# XMICRO-MEMORY.net
KiCad netlist of a schematic drawn in EAGLE
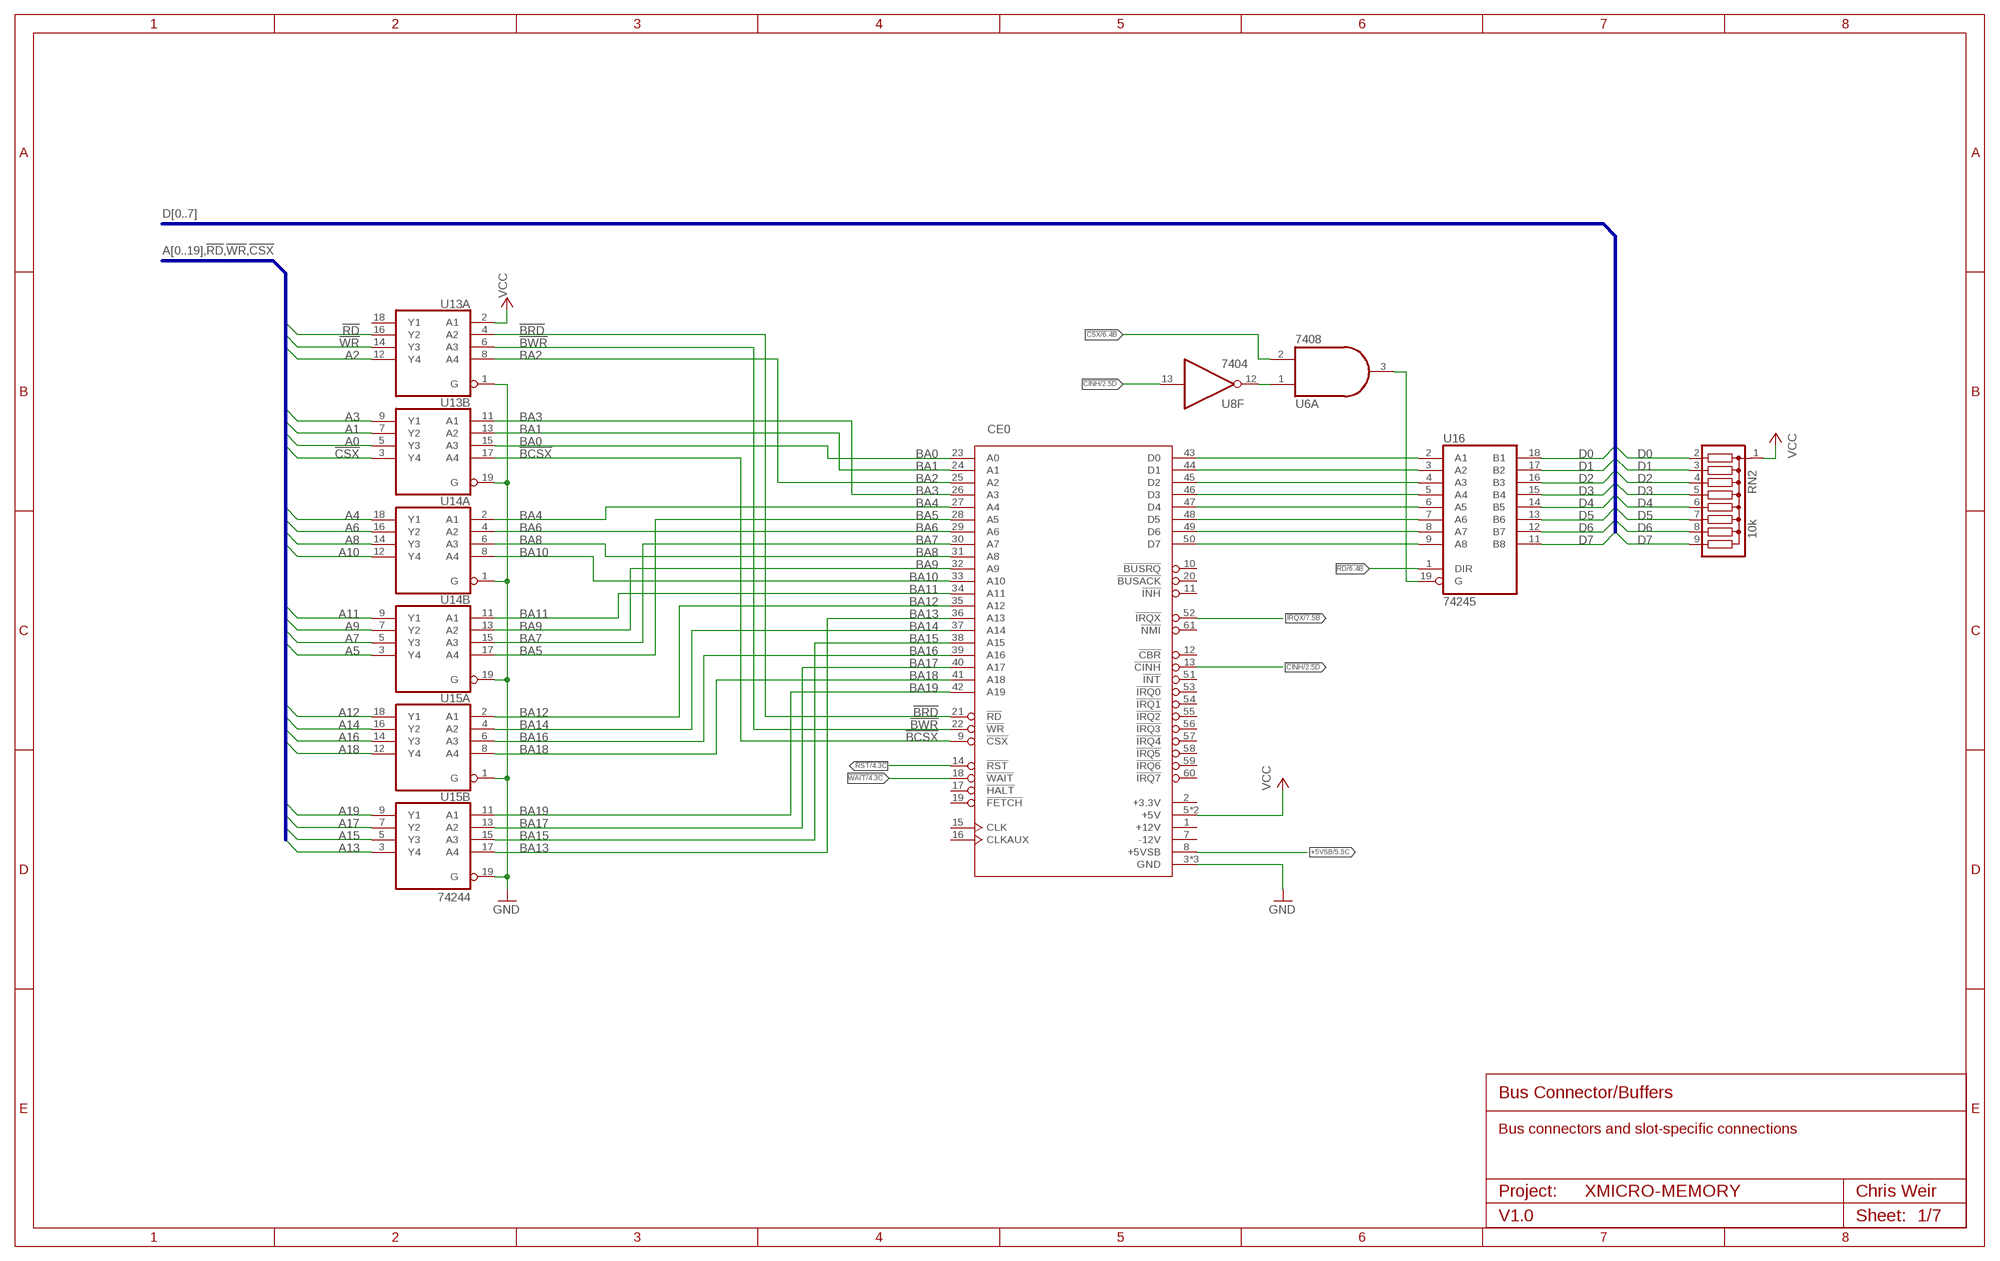
[diagram p0: schematic, sheet 1]
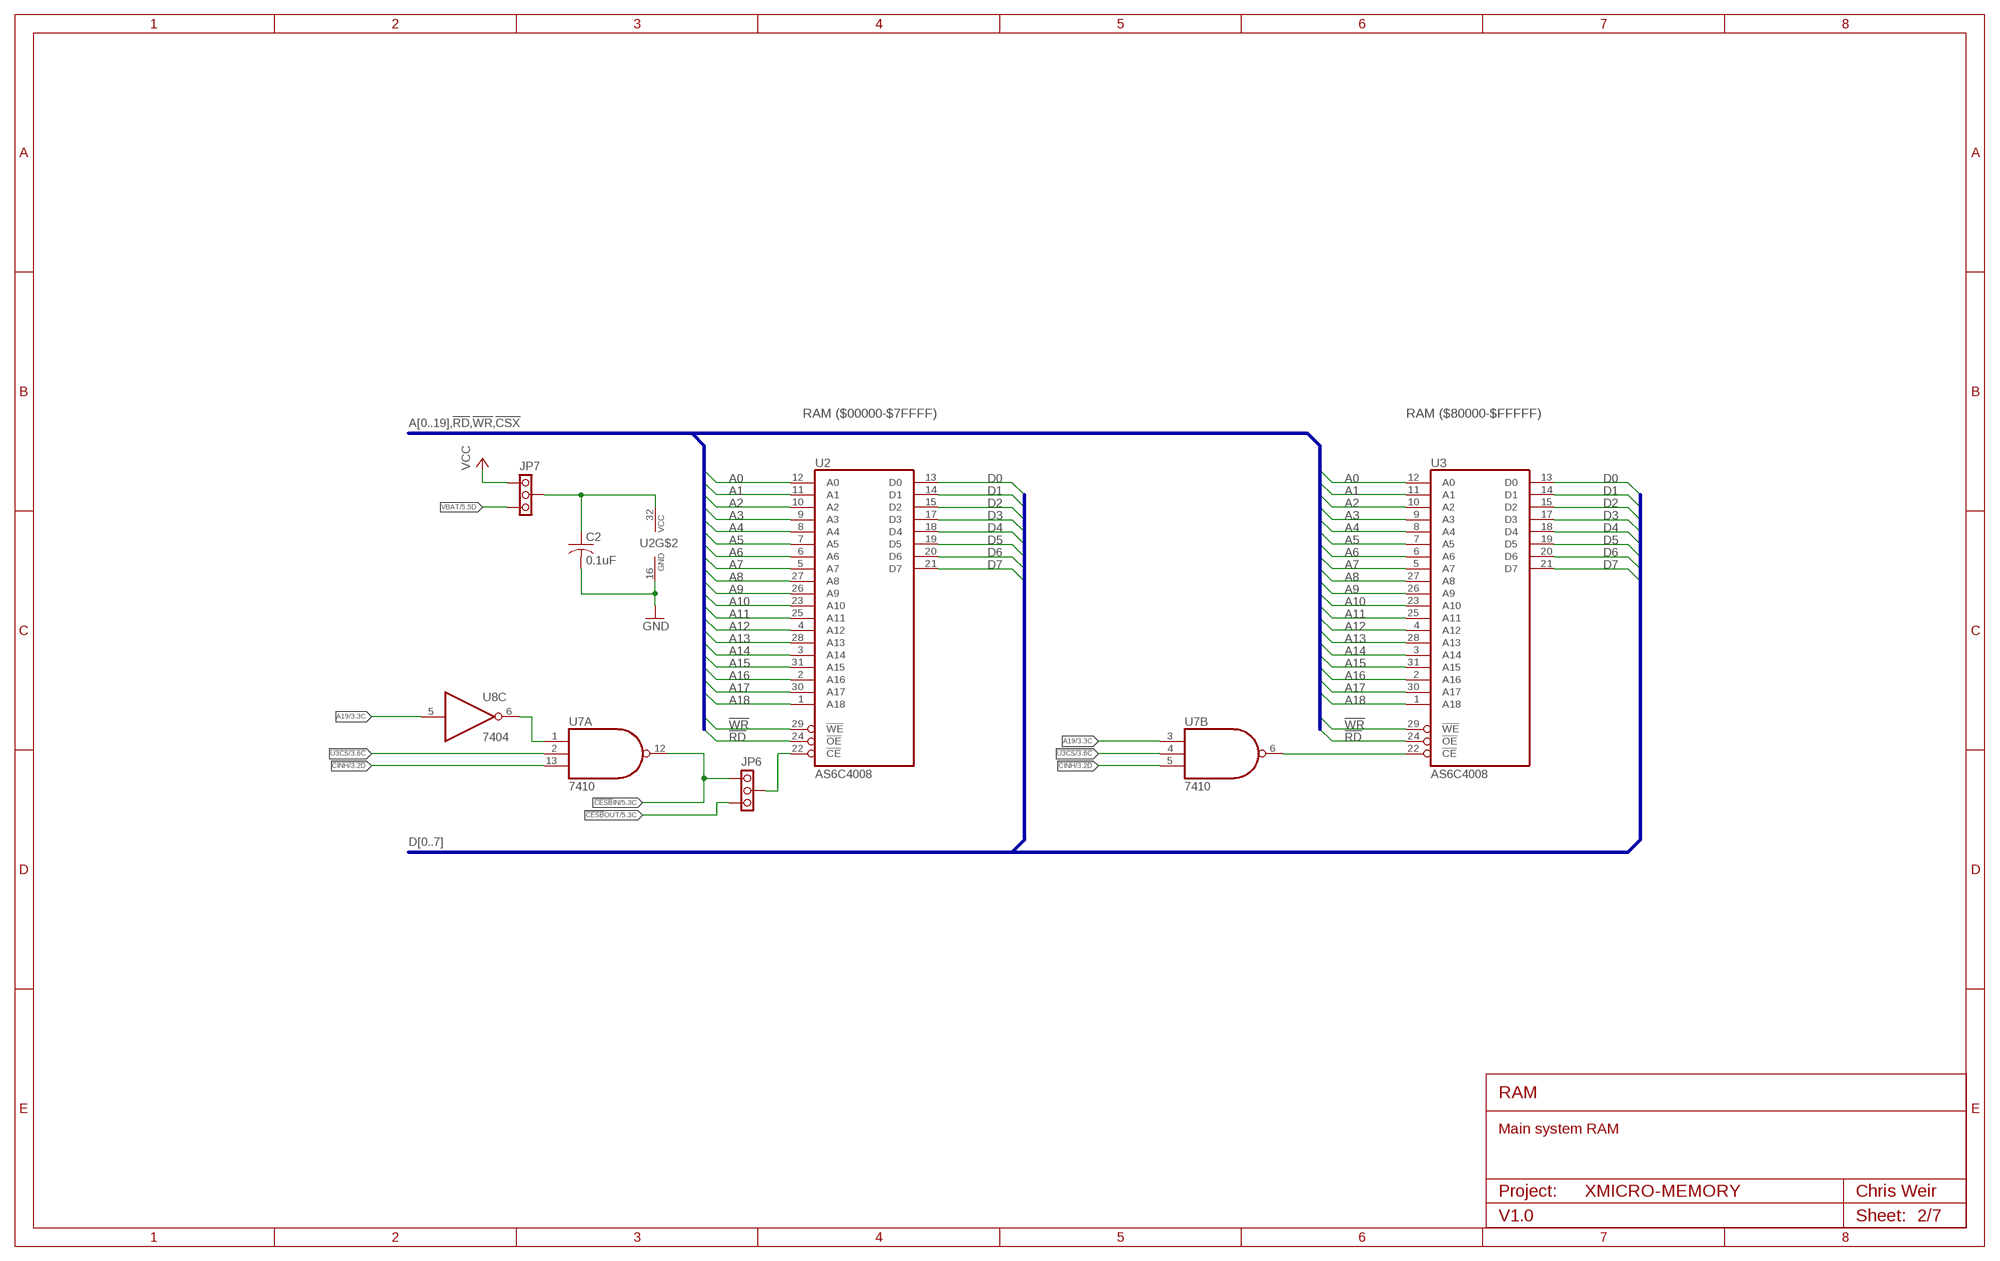
[diagram p1: schematic, sheet 2]
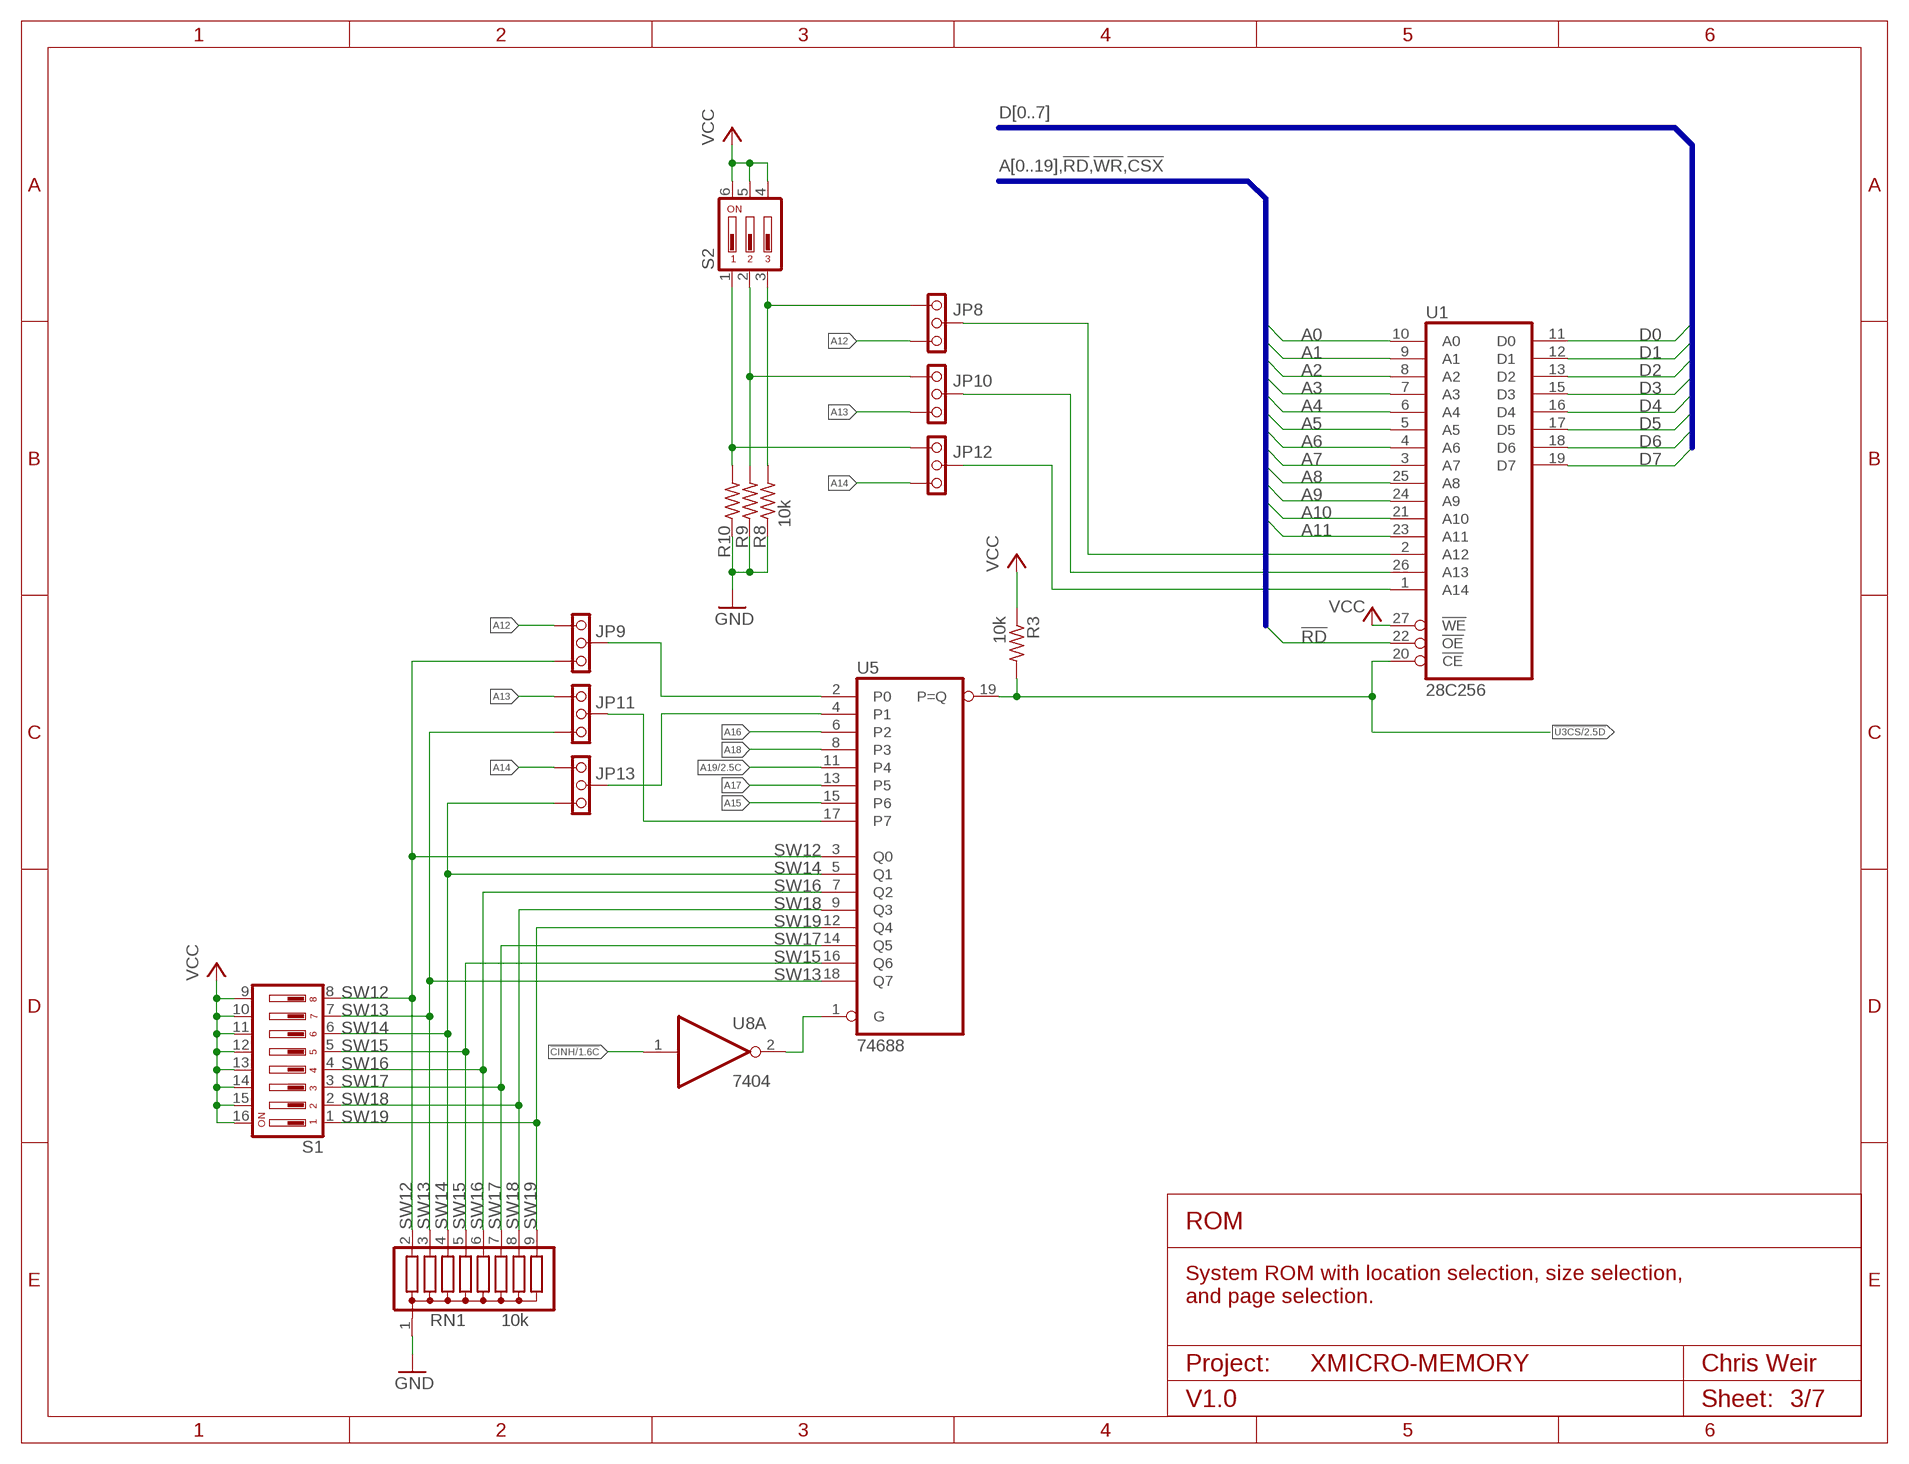
[diagram p2: schematic, sheet 3]
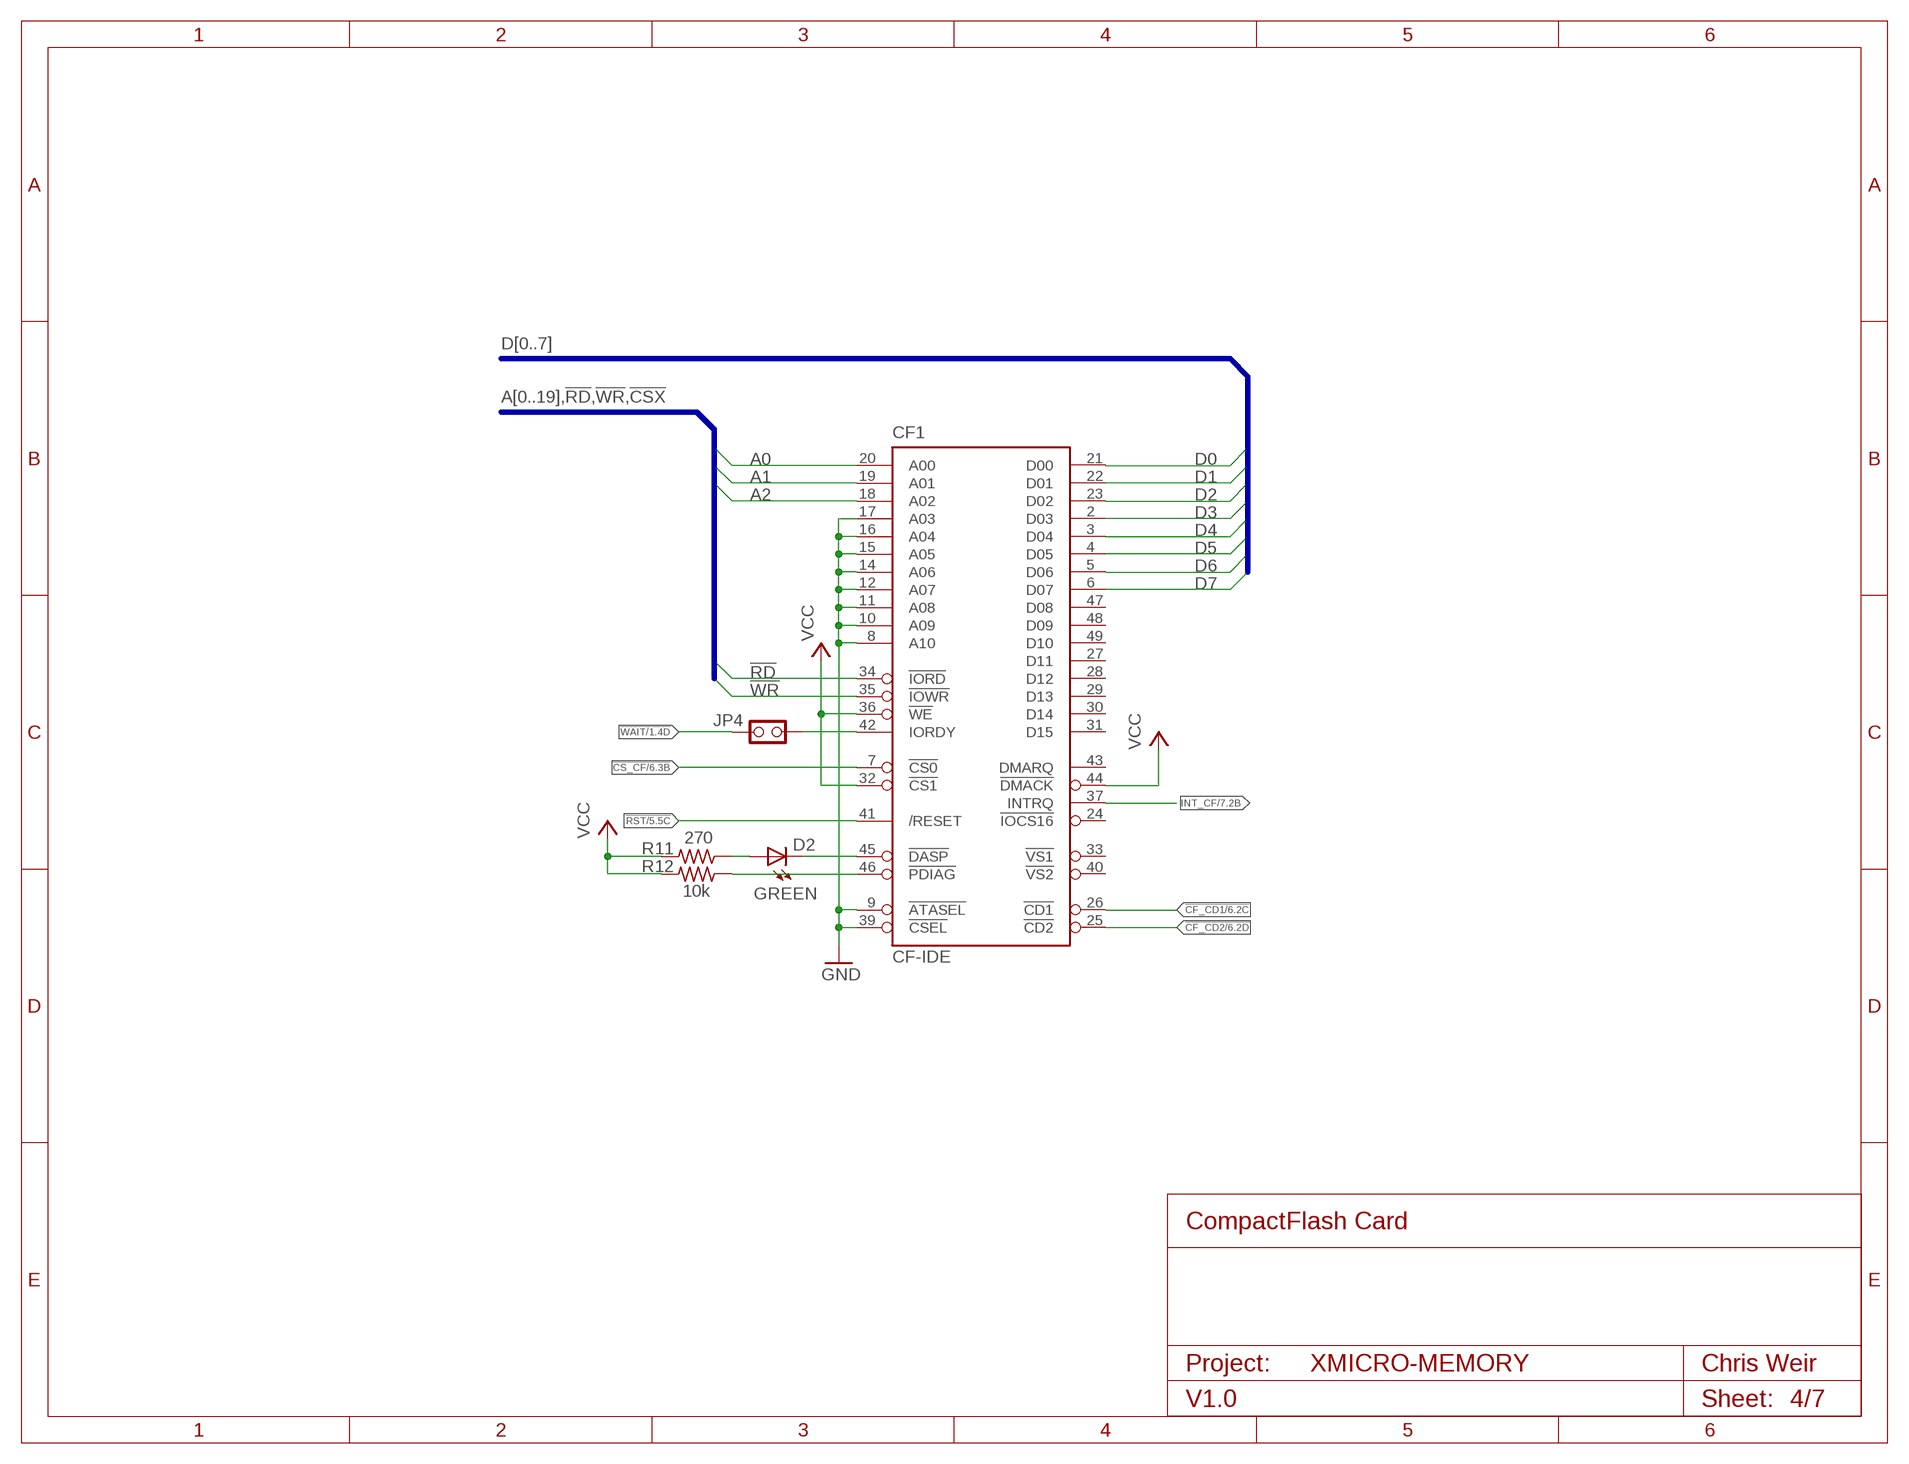
[diagram p3: schematic, sheet 4]
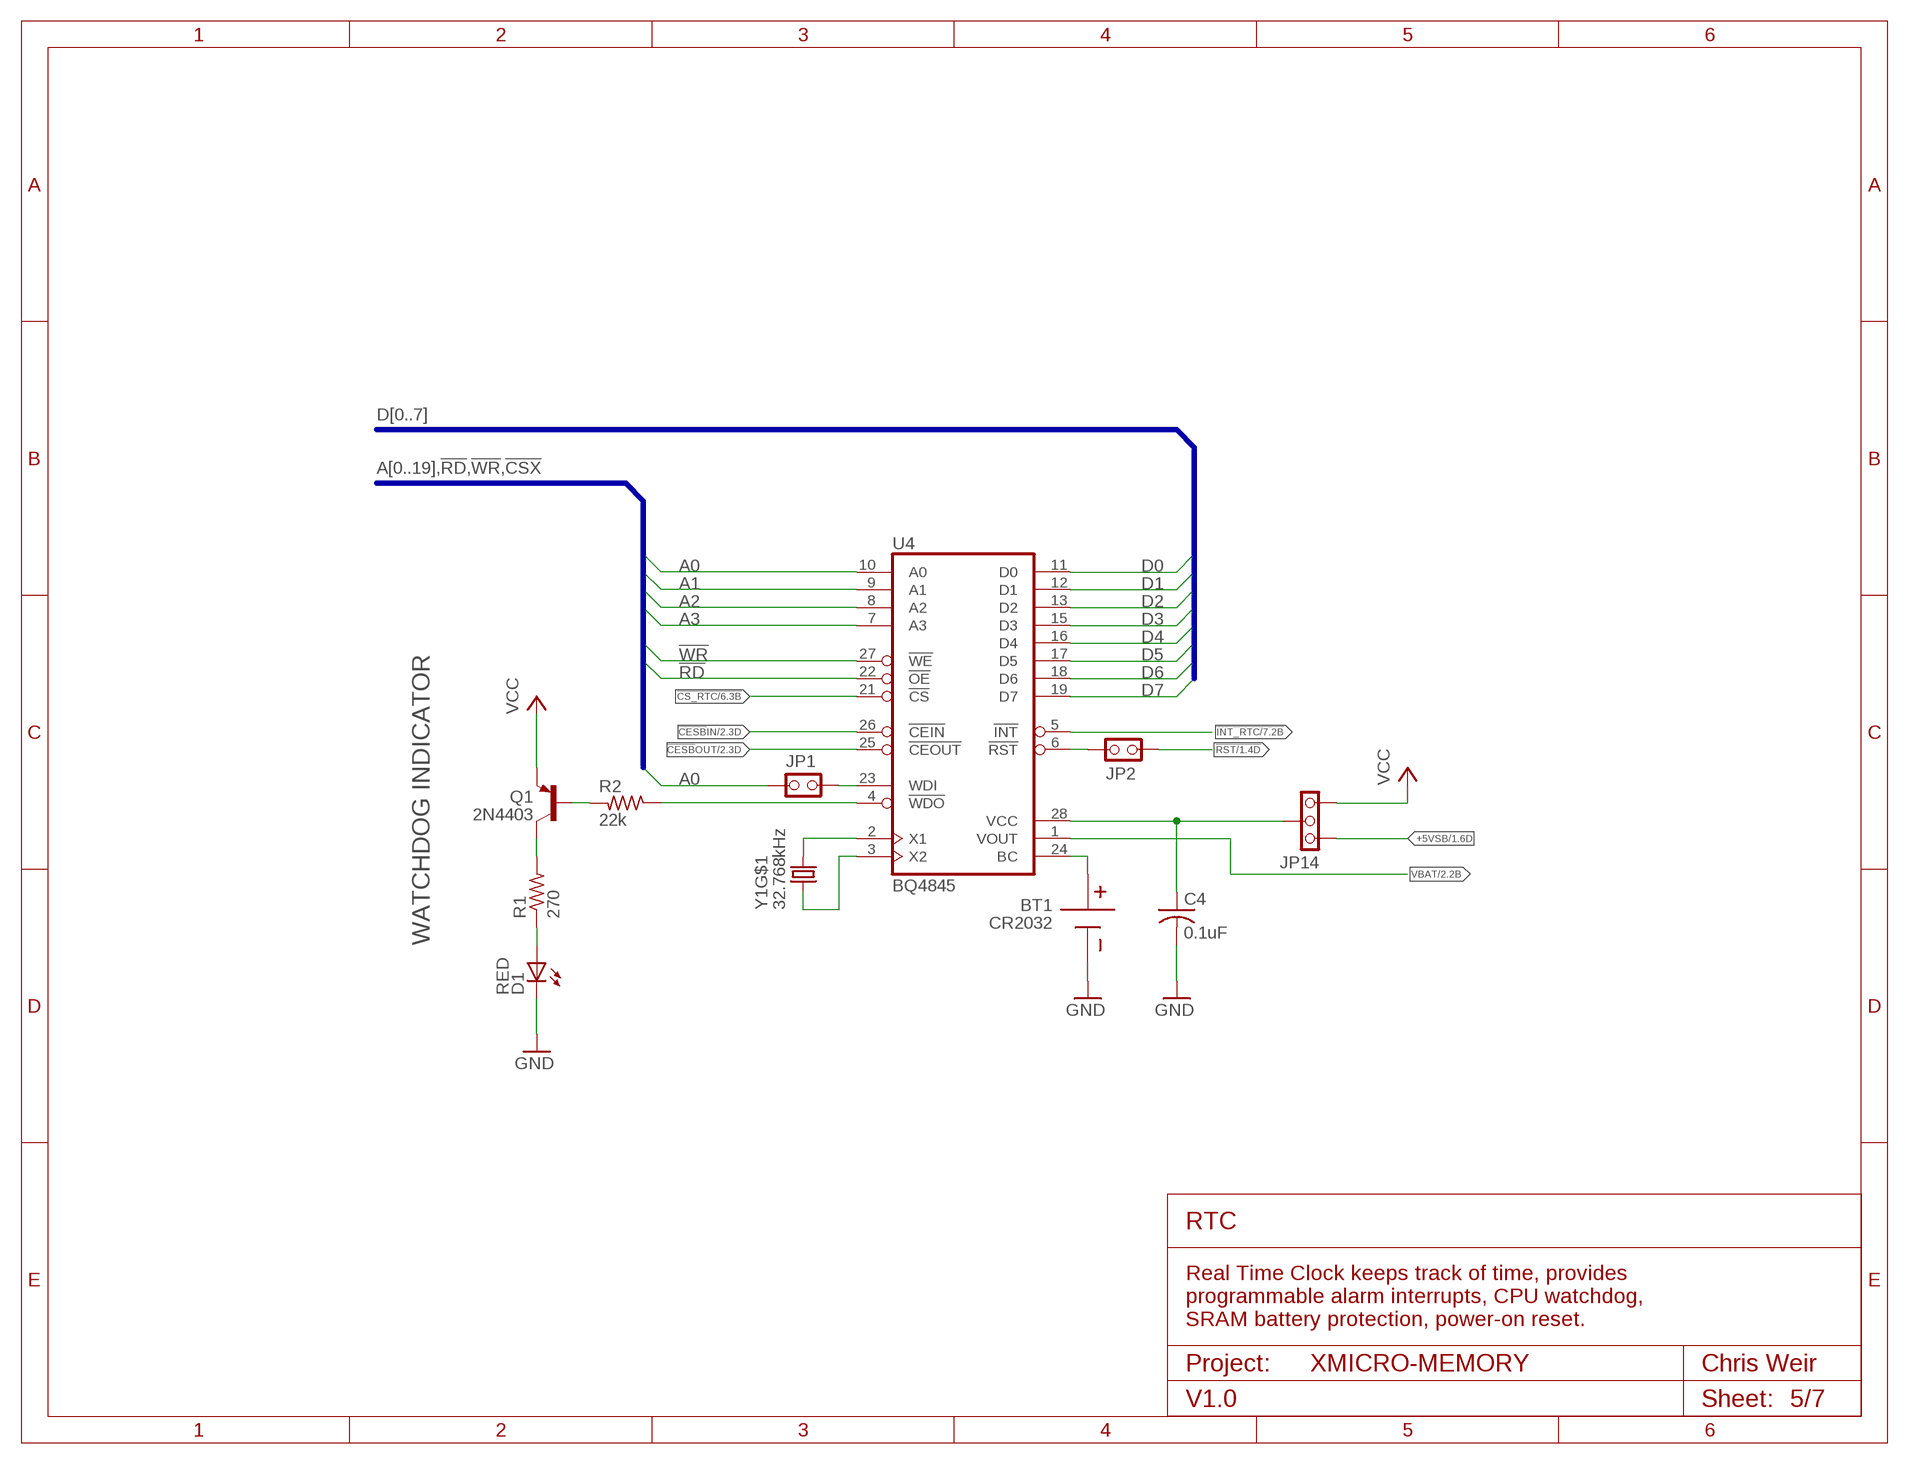
[diagram p4: schematic, sheet 5]
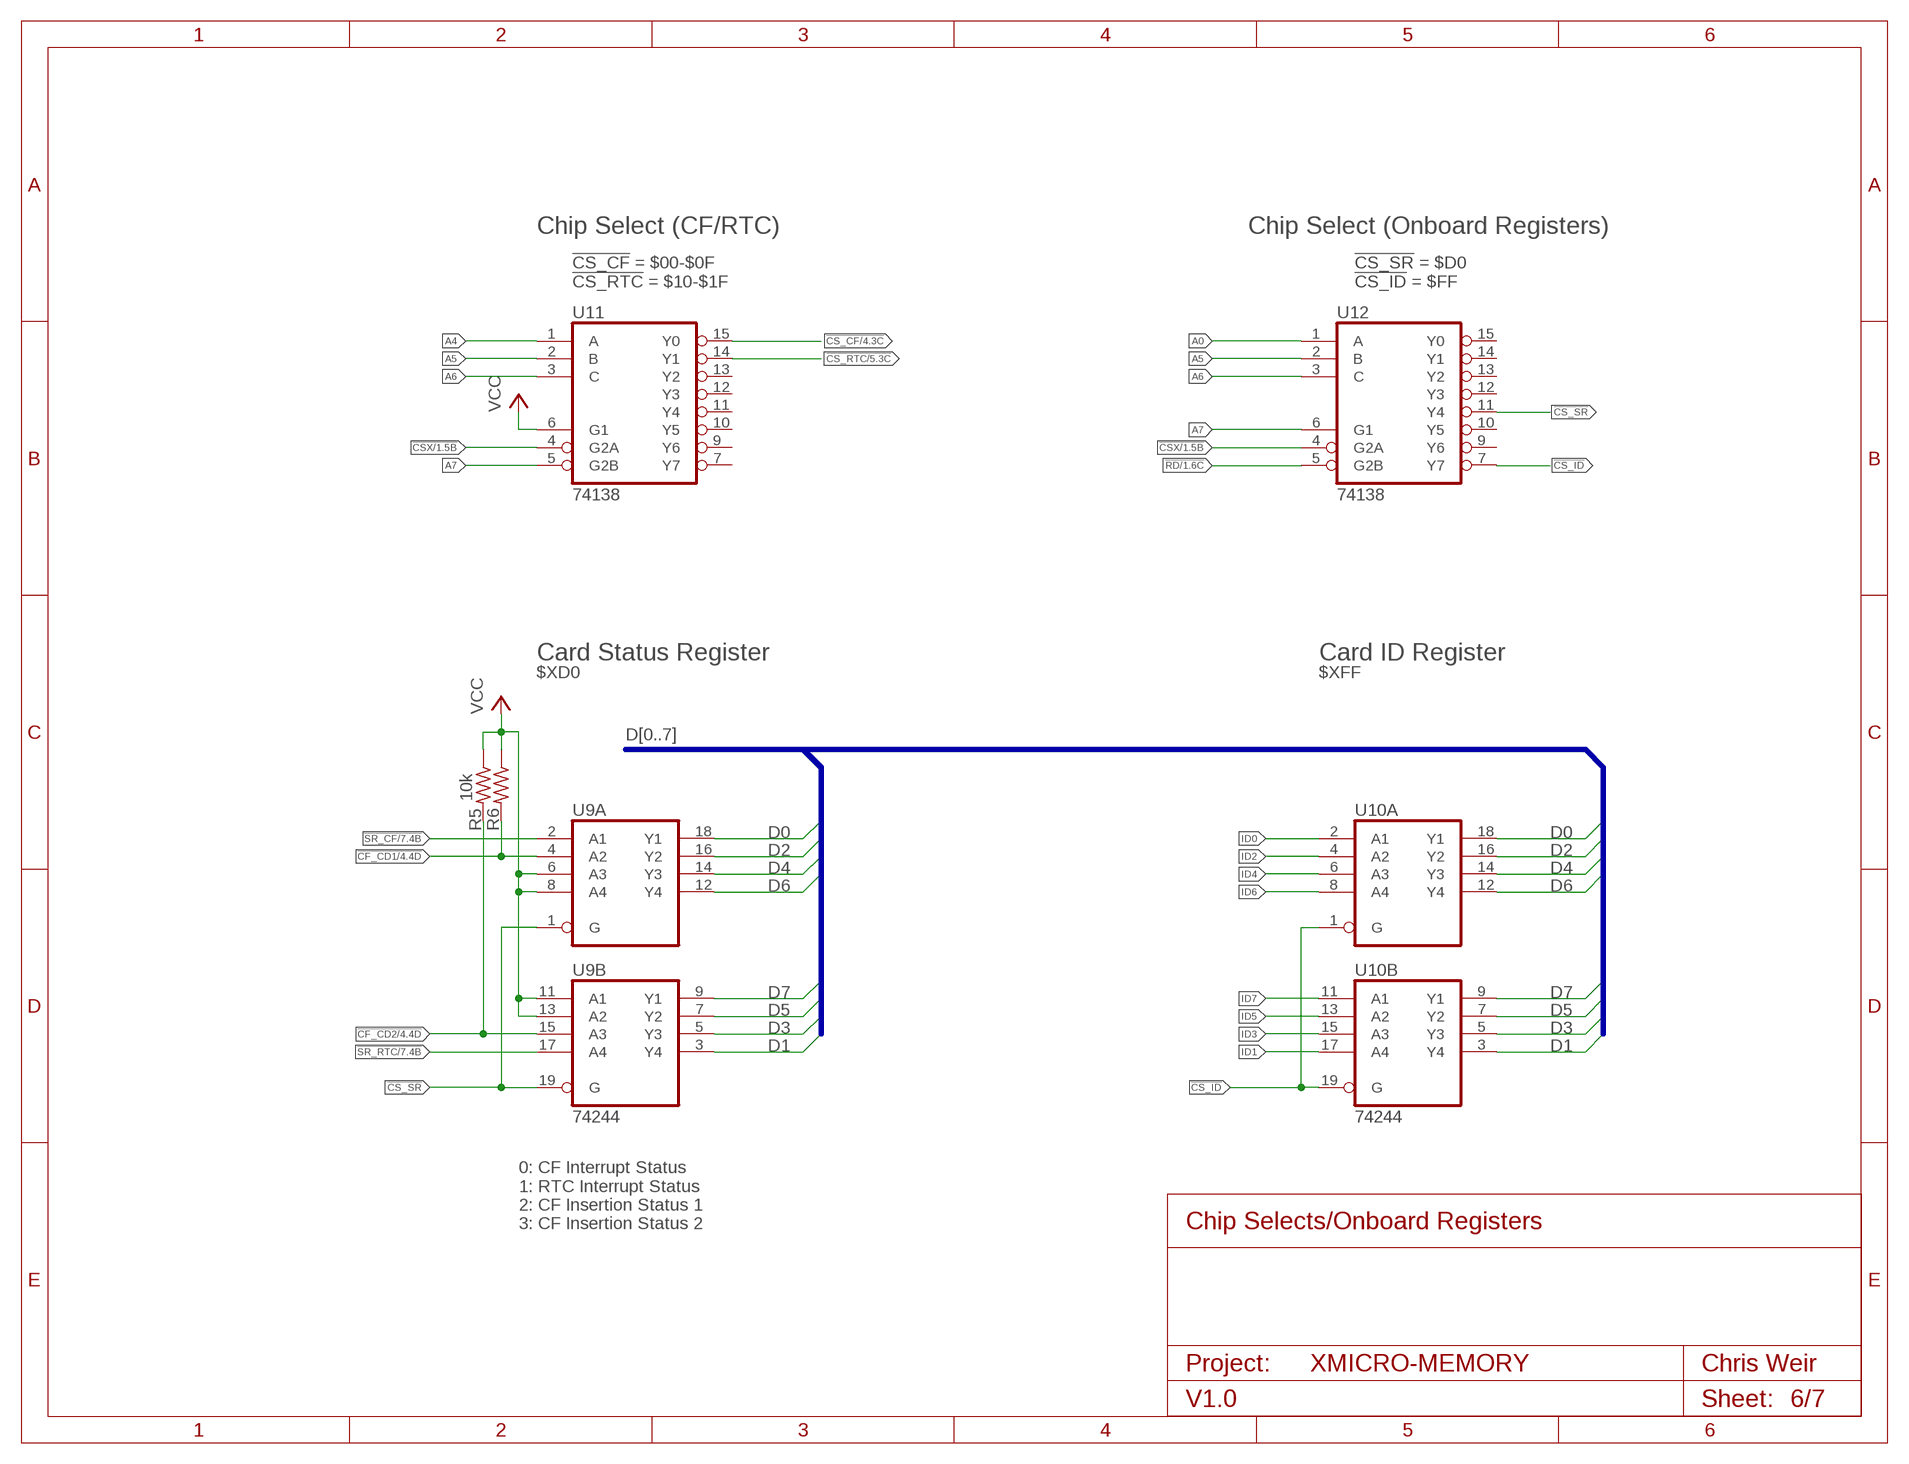
[diagram p5: schematic, sheet 6]
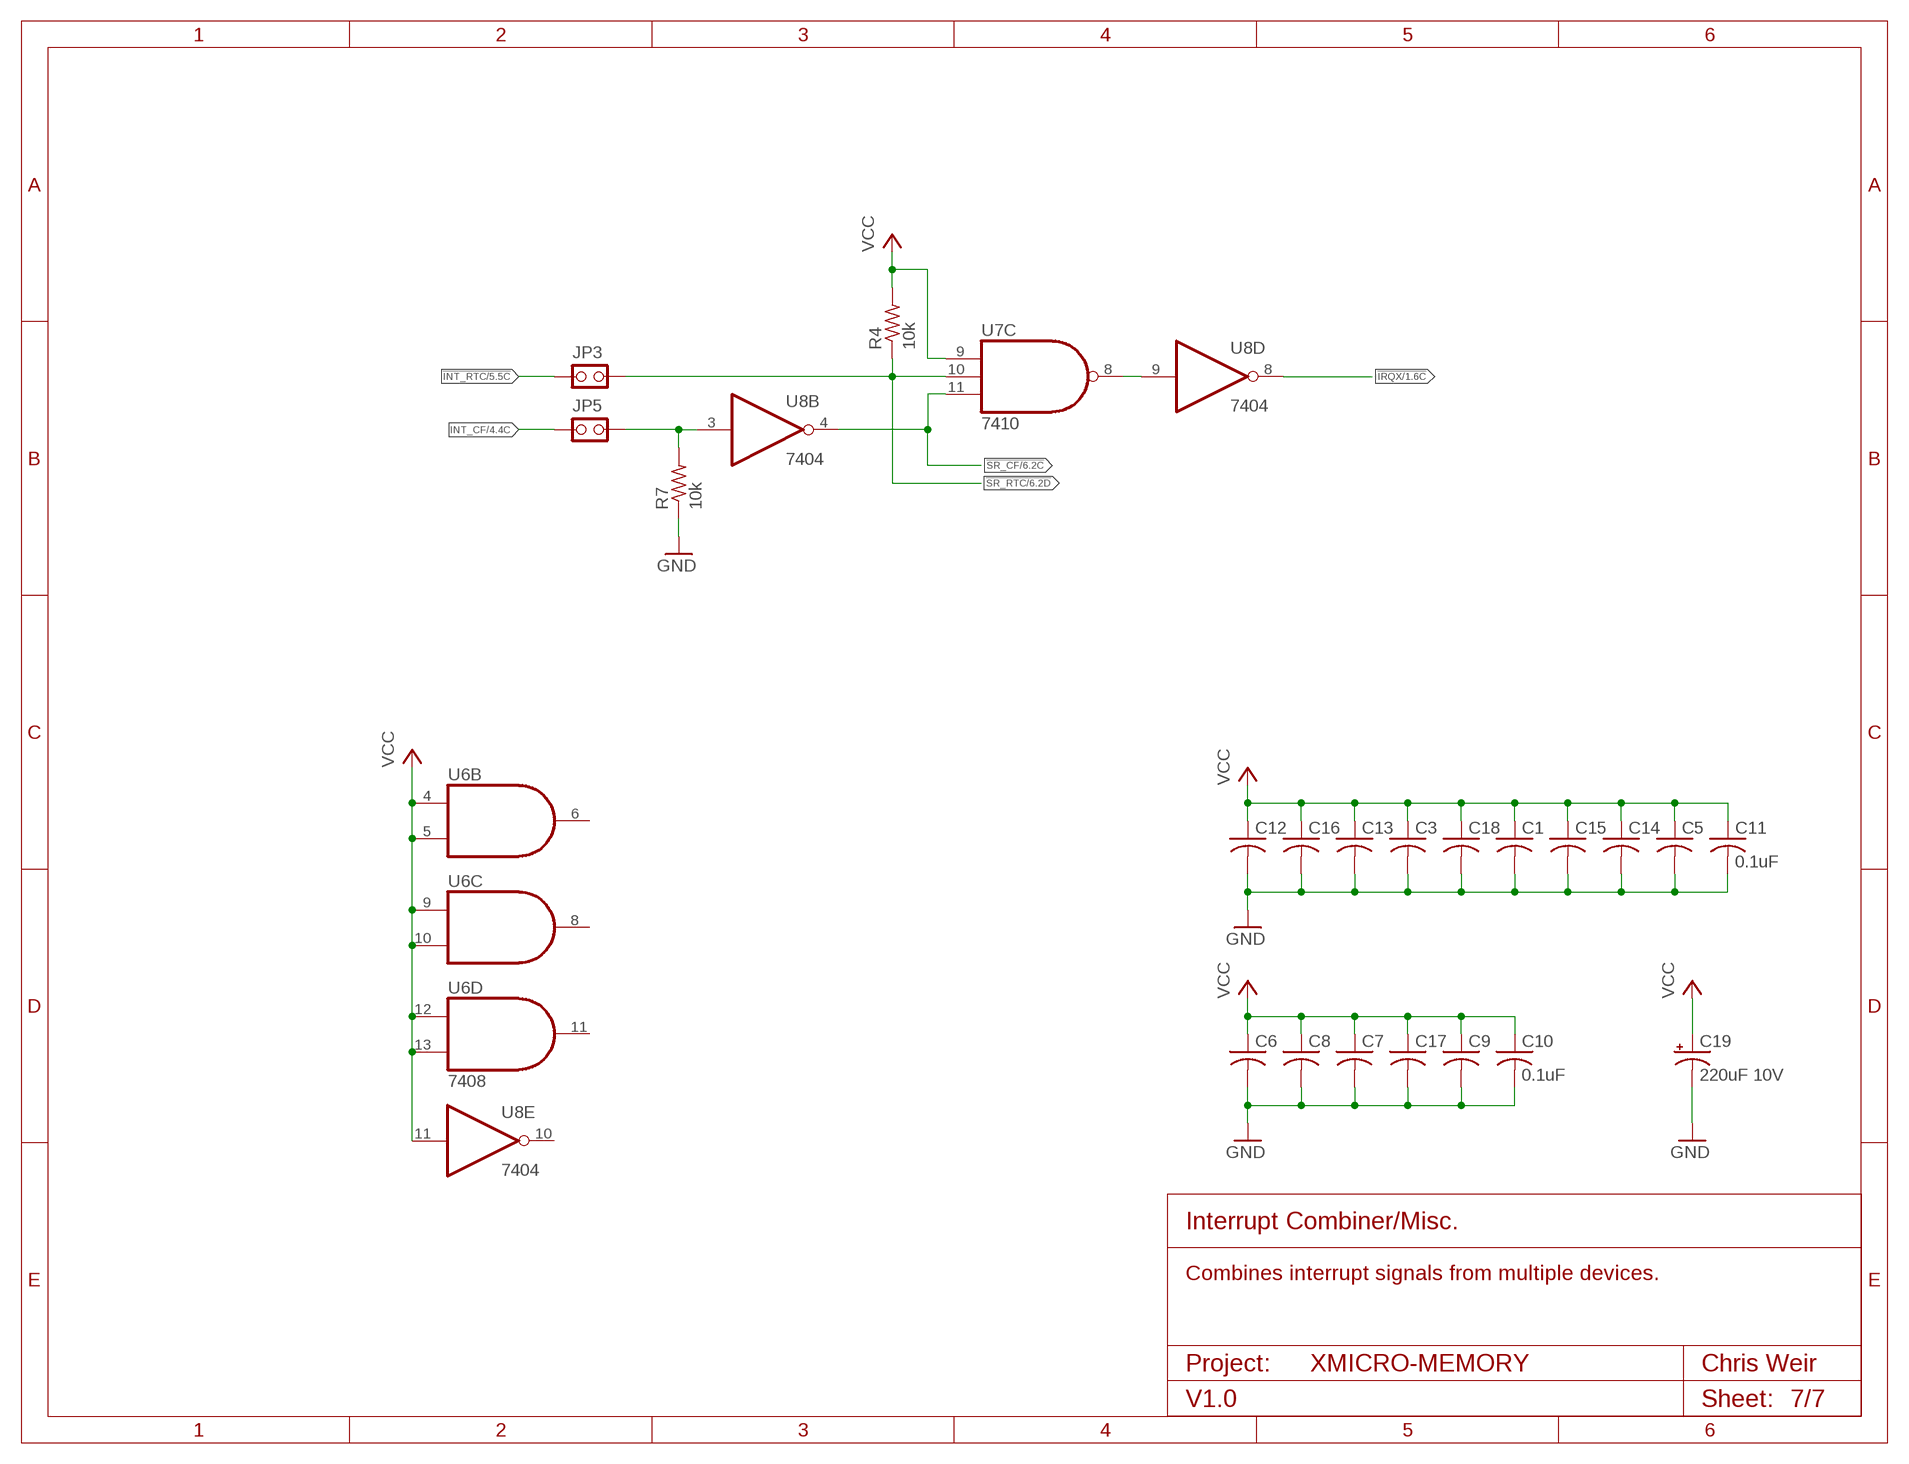
[diagram p6: schematic, sheet 7]

(export (version "E")
  (design (tool "Eeschema 10.0.6"))
  (components
    (comp (ref "CE0")
      (value "XMICRO-BUS-EDGE62M")
      (footprint "eagle-import:EDGE62M")
      (libsource (lib "eagle-import") (part "XMICRO-BUS-EDGE62M"))
    )
    (comp (ref "RN2")
      (value "10k")
      (footprint "eagle-import:SIL9")
      (fields (field (name "OC_FARNELL") "unknown") (field (name "OC_NEWARK") "unknown"))
      (libsource (lib "eagle-import") (part "G08R"))
    )
    (comp (ref "U6")
      (value "7408")
      (footprint "eagle-import:DIL14")
      (libsource (lib "eagle-import") (part "7408NLS"))
    )
    (comp (ref "U8")
      (value "7404")
      (footprint "eagle-import:DIL14")
      (libsource (lib "eagle-import") (part "7404NLS"))
    )
    (comp (ref "U13")
      (value "74244")
      (footprint "eagle-import:DIL20")
      (libsource (lib "eagle-import") (part "74244NLS"))
    )
    (comp (ref "U14")
      (value "74244")
      (footprint "eagle-import:DIL20")
      (libsource (lib "eagle-import") (part "74244NLS"))
    )
    (comp (ref "U15")
      (value "74244")
      (footprint "eagle-import:DIL20")
      (libsource (lib "eagle-import") (part "74244NLS"))
    )
    (comp (ref "U16")
      (value "74245")
      (footprint "eagle-import:DIL20")
      (libsource (lib "eagle-import") (part "74245NLS"))
    )
    (comp (ref "JP8")
      (value "PINHD1X3THRU")
      (footprint "eagle-import:1X03")
      (libsource (lib "eagle-import") (part "PINHD1X3THRU"))
    )
    (comp (ref "JP9")
      (value "PINHD1X3THRU")
      (footprint "eagle-import:1X03")
      (libsource (lib "eagle-import") (part "PINHD1X3THRU"))
    )
    (comp (ref "JP10")
      (value "PINHD1X3THRU")
      (footprint "eagle-import:1X03")
      (libsource (lib "eagle-import") (part "PINHD1X3THRU"))
    )
    (comp (ref "JP11")
      (value "PINHD1X3THRU")
      (footprint "eagle-import:1X03")
      (libsource (lib "eagle-import") (part "PINHD1X3THRU"))
    )
    (comp (ref "JP12")
      (value "PINHD1X3THRU")
      (footprint "eagle-import:1X03")
      (libsource (lib "eagle-import") (part "PINHD1X3THRU"))
    )
    (comp (ref "JP13")
      (value "PINHD1X3THRU")
      (footprint "eagle-import:1X03")
      (libsource (lib "eagle-import") (part "PINHD1X3THRU"))
    )
    (comp (ref "R3")
      (value "10k")
      (footprint "eagle-import:0207_10")
      (libsource (lib "eagle-import") (part "R-US_0207/10"))
    )
    (comp (ref "R8")
      (value "10k")
      (footprint "eagle-import:0207_10")
      (libsource (lib "eagle-import") (part "R-US_0207/10"))
    )
    (comp (ref "R9")
      (value "10k")
      (footprint "eagle-import:0207_10")
      (libsource (lib "eagle-import") (part "R-US_0207/10"))
    )
    (comp (ref "R10")
      (value "10k")
      (footprint "eagle-import:0207_10")
      (libsource (lib "eagle-import") (part "R-US_0207/10"))
    )
    (comp (ref "RN1")
      (value "10k")
      (footprint "eagle-import:SIL9")
      (libsource (lib "eagle-import") (part "G08R"))
    )
    (comp (ref "S1")
      (value "SW-DIP08")
      (footprint "eagle-import:SW-DIP8")
      (libsource (lib "eagle-import") (part "SW-DIP08"))
    )
    (comp (ref "S2")
      (value "SW-DIP03")
      (footprint "eagle-import:SW-DIP3")
      (libsource (lib "eagle-import") (part "SW-DIP03"))
    )
    (comp (ref "U1")
      (value "28C256")
      (footprint "eagle-import:228-1277-00")
      (libsource (lib "eagle-import") (part "28256-ZIF28"))
    )
    (comp (ref "U5")
      (value "74688")
      (footprint "eagle-import:DIL20")
      (libsource (lib "eagle-import") (part "74688NLS"))
    )
    (comp (ref "BT1")
      (value "CR2032")
      (footprint "eagle-import:SMTU2032")
      (libsource (lib "eagle-import") (part "CR2032SMT"))
    )
    (comp (ref "C4")
      (value "0.1uF")
      (footprint "eagle-import:C025-024X044")
      (libsource (lib "eagle-import") (part "C-US025-024X044"))
    )
    (comp (ref "D1")
      (value "RED")
      (footprint "eagle-import:LED5MM")
      (libsource (lib "eagle-import") (part "LED5MM"))
    )
    (comp (ref "JP1")
      (value "PINHD-1X2THRU")
      (footprint "eagle-import:1X02")
      (libsource (lib "eagle-import") (part "PINHD-1X2THRU"))
    )
    (comp (ref "JP2")
      (value "PINHD-1X2THRU")
      (footprint "eagle-import:1X02")
      (libsource (lib "eagle-import") (part "PINHD-1X2THRU"))
    )
    (comp (ref "JP14")
      (value "PINHD1X3THRU")
      (footprint "eagle-import:1X03")
      (libsource (lib "eagle-import") (part "PINHD1X3THRU"))
    )
    (comp (ref "Q1")
      (value "2N4403")
      (footprint "eagle-import:TO92")
      (libsource (lib "eagle-import") (part "TRANSISTOR-PNP-2N4403"))
    )
    (comp (ref "R1")
      (value "270")
      (footprint "eagle-import:0207_10")
      (libsource (lib "eagle-import") (part "R-US_0207/10"))
    )
    (comp (ref "R2")
      (value "22k")
      (footprint "eagle-import:0207_10")
      (libsource (lib "eagle-import") (part "R-US_0207/10"))
    )
    (comp (ref "U4")
      (value "BQ4845")
      (footprint "eagle-import:DIL28")
      (libsource (lib "eagle-import") (part "BQ4845"))
    )
    (comp (ref "Y1")
      (value "32.768kHz")
      (footprint "eagle-import:CRYSTAL-3X8H")
      (libsource (lib "eagle-import") (part "CRYSTAL"))
    )
    (comp (ref "C1")
      (value "0.1uF")
      (footprint "eagle-import:C025-024X044")
      (libsource (lib "eagle-import") (part "C-US025-024X044"))
    )
    (comp (ref "C3")
      (value "0.1uF")
      (footprint "eagle-import:C025-024X044")
      (libsource (lib "eagle-import") (part "C-US025-024X044"))
    )
    (comp (ref "C5")
      (value "0.1uF")
      (footprint "eagle-import:C025-024X044")
      (libsource (lib "eagle-import") (part "C-US025-024X044"))
    )
    (comp (ref "C6")
      (value "0.1uF")
      (footprint "eagle-import:C025-024X044")
      (libsource (lib "eagle-import") (part "C-US025-024X044"))
    )
    (comp (ref "C7")
      (value "0.1uF")
      (footprint "eagle-import:C025-024X044")
      (libsource (lib "eagle-import") (part "C-US025-024X044"))
    )
    (comp (ref "C8")
      (value "0.1uF")
      (footprint "eagle-import:C025-024X044")
      (libsource (lib "eagle-import") (part "C-US025-024X044"))
    )
    (comp (ref "C9")
      (value "0.1uF")
      (footprint "eagle-import:C025-024X044")
      (libsource (lib "eagle-import") (part "C-US025-024X044"))
    )
    (comp (ref "C10")
      (value "0.1uF")
      (footprint "eagle-import:C025-024X044")
      (libsource (lib "eagle-import") (part "C-US025-024X044"))
    )
    (comp (ref "C11")
      (value "0.1uF")
      (footprint "eagle-import:C025-024X044")
      (libsource (lib "eagle-import") (part "C-US025-024X044"))
    )
    (comp (ref "C12")
      (value "0.1uF")
      (footprint "eagle-import:C025-024X044")
      (libsource (lib "eagle-import") (part "C-US025-024X044"))
    )
    (comp (ref "C13")
      (value "0.1uF")
      (footprint "eagle-import:C025-024X044")
      (libsource (lib "eagle-import") (part "C-US025-024X044"))
    )
    (comp (ref "C14")
      (value "0.1uF")
      (footprint "eagle-import:C025-024X044")
      (libsource (lib "eagle-import") (part "C-US025-024X044"))
    )
    (comp (ref "C15")
      (value "0.1uF")
      (footprint "eagle-import:C025-024X044")
      (libsource (lib "eagle-import") (part "C-US025-024X044"))
    )
    (comp (ref "C16")
      (value "0.1uF")
      (footprint "eagle-import:C025-024X044")
      (libsource (lib "eagle-import") (part "C-US025-024X044"))
    )
    (comp (ref "C17")
      (value "0.1uF")
      (footprint "eagle-import:C025-024X044")
      (libsource (lib "eagle-import") (part "C-US025-024X044"))
    )
    (comp (ref "C18")
      (value "0.1uF")
      (footprint "eagle-import:C025-024X044")
      (libsource (lib "eagle-import") (part "C-US025-024X044"))
    )
    (comp (ref "C19")
      (value "220uF 10V")
      (footprint "eagle-import:C-10-5")
      (libsource (lib "eagle-import") (part "CPOL-US-10-5"))
    )
    (comp (ref "JP3")
      (value "PINHD-1X2THRU")
      (footprint "eagle-import:1X02")
      (libsource (lib "eagle-import") (part "PINHD-1X2THRU"))
    )
    (comp (ref "JP5")
      (value "PINHD-1X2THRU")
      (footprint "eagle-import:1X02")
      (libsource (lib "eagle-import") (part "PINHD-1X2THRU"))
    )
    (comp (ref "R4")
      (value "10k")
      (footprint "eagle-import:0207_10")
      (libsource (lib "eagle-import") (part "R-US_0207/10"))
    )
    (comp (ref "R7")
      (value "10k")
      (footprint "eagle-import:0207_10")
      (libsource (lib "eagle-import") (part "R-US_0207/10"))
    )
    (comp (ref "U7")
      (value "7410")
      (footprint "eagle-import:DIL14")
      (libsource (lib "eagle-import") (part "7410NLS"))
    )
    (comp (ref "CF1")
      (value "CF-IDE")
      (footprint "eagle-import:CF-KYOCERA")
      (libsource (lib "eagle-import") (part "CF-IDE"))
    )
    (comp (ref "D2")
      (value "GREEN")
      (footprint "eagle-import:LED-3-R")
      (libsource (lib "eagle-import") (part "LED-3-R"))
    )
    (comp (ref "JP4")
      (value "PINHD-1X2THRU")
      (footprint "eagle-import:1X02")
      (libsource (lib "eagle-import") (part "PINHD-1X2THRU"))
    )
    (comp (ref "R11")
      (value "270")
      (footprint "eagle-import:0207_10")
      (libsource (lib "eagle-import") (part "R-US_0207/10"))
    )
    (comp (ref "R12")
      (value "10k")
      (footprint "eagle-import:0207_10")
      (libsource (lib "eagle-import") (part "R-US_0207/10"))
    )
    (comp (ref "C2")
      (value "0.1uF")
      (footprint "eagle-import:C025-024X044")
      (libsource (lib "eagle-import") (part "C-US025-024X044"))
    )
    (comp (ref "JP6")
      (value "PINHD1X3THRU")
      (footprint "eagle-import:1X03")
      (libsource (lib "eagle-import") (part "PINHD1X3THRU"))
    )
    (comp (ref "JP7")
      (value "PINHD1X3THRU")
      (footprint "eagle-import:1X03")
      (libsource (lib "eagle-import") (part "PINHD1X3THRU"))
    )
    (comp (ref "U2")
      (value "AS6C4008")
      (footprint "eagle-import:DIL32-6")
      (libsource (lib "eagle-import") (part "4008"))
    )
    (comp (ref "U3")
      (value "AS6C4008")
      (footprint "eagle-import:DIL32-6")
      (libsource (lib "eagle-import") (part "4008"))
    )
    (comp (ref "R5")
      (value "10k")
      (footprint "eagle-import:0207_10")
      (libsource (lib "eagle-import") (part "R-US_0207/10"))
    )
    (comp (ref "R6")
      (value "10k")
      (footprint "eagle-import:0207_10")
      (libsource (lib "eagle-import") (part "R-US_0207/10"))
    )
    (comp (ref "U9")
      (value "74244")
      (footprint "eagle-import:DIL20")
      (libsource (lib "eagle-import") (part "74244NLS"))
    )
    (comp (ref "U10")
      (value "74244")
      (footprint "eagle-import:DIL20")
      (libsource (lib "eagle-import") (part "74244NLS"))
    )
    (comp (ref "U11")
      (value "74138")
      (footprint "eagle-import:DIL16")
      (libsource (lib "eagle-import") (part "74138NLS"))
    )
    (comp (ref "U12")
      (value "74138")
      (footprint "eagle-import:DIL16")
      (libsource (lib "eagle-import") (part "74138NLS"))
    )
  )
  (nets
    (net (code "6") (name "+5VSB") (class "Default")
      (node (ref "CE0") (pin "8") (pinfunction "+5VSB_8") (pintype "bidirectional"))
      (node (ref "JP14") (pin "1") (pinfunction "1_1") (pintype "passive"))
    )
    (net (code "18") (name "A0") (class "Default")
      (node (ref "CF1") (pin "20") (pinfunction "A00_20") (pintype "input"))
      (node (ref "JP1") (pin "1") (pinfunction "1_1") (pintype "passive"))
      (node (ref "U1") (pin "10") (pinfunction "A0_10") (pintype "input"))
      (node (ref "U12") (pin "1") (pinfunction "A_1") (pintype "input"))
      (node (ref "U13") (pin "5") (pinfunction "Y3_5") (pintype "tri_state"))
      (node (ref "U2") (pin "12") (pinfunction "A0_12") (pintype "input"))
      (node (ref "U3") (pin "12") (pinfunction "A0_12") (pintype "input"))
      (node (ref "U4") (pin "10") (pinfunction "A0_10") (pintype "input"))
    )
    (net (code "19") (name "A1") (class "Default")
      (node (ref "CF1") (pin "19") (pinfunction "A01_19") (pintype "input"))
      (node (ref "U1") (pin "9") (pinfunction "A1_9") (pintype "input"))
      (node (ref "U13") (pin "7") (pinfunction "Y2_7") (pintype "tri_state"))
      (node (ref "U2") (pin "11") (pinfunction "A1_11") (pintype "input"))
      (node (ref "U3") (pin "11") (pinfunction "A1_11") (pintype "input"))
      (node (ref "U4") (pin "9") (pinfunction "A1_9") (pintype "input"))
    )
    (net (code "20") (name "A2") (class "Default")
      (node (ref "CF1") (pin "18") (pinfunction "A02_18") (pintype "input"))
      (node (ref "U1") (pin "8") (pinfunction "A2_8") (pintype "input"))
      (node (ref "U13") (pin "12") (pinfunction "Y4_12") (pintype "tri_state"))
      (node (ref "U2") (pin "10") (pinfunction "A2_10") (pintype "input"))
      (node (ref "U3") (pin "10") (pinfunction "A2_10") (pintype "input"))
      (node (ref "U4") (pin "8") (pinfunction "A2_8") (pintype "input"))
    )
    (net (code "21") (name "A3") (class "Default")
      (node (ref "U1") (pin "7") (pinfunction "A3_7") (pintype "input"))
      (node (ref "U13") (pin "9") (pinfunction "Y1_9") (pintype "tri_state"))
      (node (ref "U2") (pin "9") (pinfunction "A3_9") (pintype "input"))
      (node (ref "U3") (pin "9") (pinfunction "A3_9") (pintype "input"))
      (node (ref "U4") (pin "7") (pinfunction "A3_7") (pintype "input"))
    )
    (net (code "22") (name "A4") (class "Default")
      (node (ref "U1") (pin "6") (pinfunction "A4_6") (pintype "input"))
      (node (ref "U11") (pin "1") (pinfunction "A_1") (pintype "input"))
      (node (ref "U14") (pin "18") (pinfunction "Y1_18") (pintype "tri_state"))
      (node (ref "U2") (pin "8") (pinfunction "A4_8") (pintype "input"))
      (node (ref "U3") (pin "8") (pinfunction "A4_8") (pintype "input"))
    )
    (net (code "23") (name "A5") (class "Default")
      (node (ref "U1") (pin "5") (pinfunction "A5_5") (pintype "input"))
      (node (ref "U11") (pin "2") (pinfunction "B_2") (pintype "input"))
      (node (ref "U12") (pin "2") (pinfunction "B_2") (pintype "input"))
      (node (ref "U14") (pin "3") (pinfunction "Y4_3") (pintype "tri_state"))
      (node (ref "U2") (pin "7") (pinfunction "A5_7") (pintype "input"))
      (node (ref "U3") (pin "7") (pinfunction "A5_7") (pintype "input"))
    )
    (net (code "24") (name "A6") (class "Default")
      (node (ref "U1") (pin "4") (pinfunction "A6_4") (pintype "input"))
      (node (ref "U11") (pin "3") (pinfunction "C_3") (pintype "input"))
      (node (ref "U12") (pin "3") (pinfunction "C_3") (pintype "input"))
      (node (ref "U14") (pin "16") (pinfunction "Y2_16") (pintype "tri_state"))
      (node (ref "U2") (pin "6") (pinfunction "A6_6") (pintype "input"))
      (node (ref "U3") (pin "6") (pinfunction "A6_6") (pintype "input"))
    )
    (net (code "25") (name "A7") (class "Default")
      (node (ref "U1") (pin "3") (pinfunction "A7_3") (pintype "input"))
      (node (ref "U11") (pin "5") (pinfunction "G2B_5") (pintype "input"))
      (node (ref "U12") (pin "6") (pinfunction "G1_6") (pintype "input"))
      (node (ref "U14") (pin "5") (pinfunction "Y3_5") (pintype "tri_state"))
      (node (ref "U2") (pin "5") (pinfunction "A7_5") (pintype "input"))
      (node (ref "U3") (pin "5") (pinfunction "A7_5") (pintype "input"))
    )
    (net (code "26") (name "A8") (class "Default")
      (node (ref "U1") (pin "25") (pinfunction "A8_25") (pintype "input"))
      (node (ref "U14") (pin "14") (pinfunction "Y3_14") (pintype "tri_state"))
      (node (ref "U2") (pin "27") (pinfunction "A8_27") (pintype "input"))
      (node (ref "U3") (pin "27") (pinfunction "A8_27") (pintype "input"))
    )
    (net (code "27") (name "A9") (class "Default")
      (node (ref "U1") (pin "24") (pinfunction "A9_24") (pintype "input"))
      (node (ref "U14") (pin "7") (pinfunction "Y2_7") (pintype "tri_state"))
      (node (ref "U2") (pin "26") (pinfunction "A9_26") (pintype "input"))
      (node (ref "U3") (pin "26") (pinfunction "A9_26") (pintype "input"))
    )
    (net (code "28") (name "A10") (class "Default")
      (node (ref "U1") (pin "21") (pinfunction "A10_21") (pintype "input"))
      (node (ref "U14") (pin "12") (pinfunction "Y4_12") (pintype "tri_state"))
      (node (ref "U2") (pin "23") (pinfunction "A10_23") (pintype "input"))
      (node (ref "U3") (pin "23") (pinfunction "A10_23") (pintype "input"))
    )
    (net (code "29") (name "A11") (class "Default")
      (node (ref "U1") (pin "23") (pinfunction "A11_23") (pintype "input"))
      (node (ref "U14") (pin "9") (pinfunction "Y1_9") (pintype "tri_state"))
      (node (ref "U2") (pin "25") (pinfunction "A11_25") (pintype "input"))
      (node (ref "U3") (pin "25") (pinfunction "A11_25") (pintype "input"))
    )
    (net (code "30") (name "A12") (class "Default")
      (node (ref "JP8") (pin "3") (pinfunction "3_3") (pintype "passive"))
      (node (ref "JP9") (pin "1") (pinfunction "1_1") (pintype "passive"))
      (node (ref "U15") (pin "18") (pinfunction "Y1_18") (pintype "tri_state"))
      (node (ref "U2") (pin "4") (pinfunction "A12_4") (pintype "input"))
      (node (ref "U3") (pin "4") (pinfunction "A12_4") (pintype "input"))
    )
    (net (code "31") (name "A13") (class "Default")
      (node (ref "JP10") (pin "3") (pinfunction "3_3") (pintype "passive"))
      (node (ref "JP11") (pin "1") (pinfunction "1_1") (pintype "passive"))
      (node (ref "U15") (pin "3") (pinfunction "Y4_3") (pintype "tri_state"))
      (node (ref "U2") (pin "28") (pinfunction "A13_28") (pintype "input"))
      (node (ref "U3") (pin "28") (pinfunction "A13_28") (pintype "input"))
    )
    (net (code "32") (name "A14") (class "Default")
      (node (ref "JP12") (pin "3") (pinfunction "3_3") (pintype "passive"))
      (node (ref "JP13") (pin "1") (pinfunction "1_1") (pintype "passive"))
      (node (ref "U15") (pin "16") (pinfunction "Y2_16") (pintype "tri_state"))
      (node (ref "U2") (pin "3") (pinfunction "A14_3") (pintype "input"))
      (node (ref "U3") (pin "3") (pinfunction "A14_3") (pintype "input"))
    )
    (net (code "33") (name "A15") (class "Default")
      (node (ref "U15") (pin "5") (pinfunction "Y3_5") (pintype "tri_state"))
      (node (ref "U2") (pin "31") (pinfunction "A15_31") (pintype "input"))
      (node (ref "U3") (pin "31") (pinfunction "A15_31") (pintype "input"))
      (node (ref "U5") (pin "15") (pinfunction "P6_15") (pintype "input"))
    )
    (net (code "34") (name "A16") (class "Default")
      (node (ref "U15") (pin "14") (pinfunction "Y3_14") (pintype "tri_state"))
      (node (ref "U2") (pin "2") (pinfunction "A16_2") (pintype "input"))
      (node (ref "U3") (pin "2") (pinfunction "A16_2") (pintype "input"))
      (node (ref "U5") (pin "6") (pinfunction "P2_6") (pintype "input"))
    )
    (net (code "35") (name "A17") (class "Default")
      (node (ref "U15") (pin "7") (pinfunction "Y2_7") (pintype "tri_state"))
      (node (ref "U2") (pin "30") (pinfunction "A17_30") (pintype "input"))
      (node (ref "U3") (pin "30") (pinfunction "A17_30") (pintype "input"))
      (node (ref "U5") (pin "13") (pinfunction "P5_13") (pintype "input"))
    )
    (net (code "36") (name "A18") (class "Default")
      (node (ref "U15") (pin "12") (pinfunction "Y4_12") (pintype "tri_state"))
      (node (ref "U2") (pin "1") (pinfunction "A18_1") (pintype "input"))
      (node (ref "U3") (pin "1") (pinfunction "A18_1") (pintype "input"))
      (node (ref "U5") (pin "8") (pinfunction "P3_8") (pintype "input"))
    )
    (net (code "37") (name "A19") (class "Default")
      (node (ref "U15") (pin "9") (pinfunction "Y1_9") (pintype "tri_state"))
      (node (ref "U5") (pin "11") (pinfunction "P4_11") (pintype "input"))
      (node (ref "U7") (pin "3") (pinfunction "I0_3") (pintype "input"))
      (node (ref "U8") (pin "5") (pinfunction "I_5") (pintype "input"))
    )
    (net (code "38") (name "BA0") (class "Default")
      (node (ref "CE0") (pin "23") (pinfunction "A0_23") (pintype "bidirectional"))
      (node (ref "U13") (pin "15") (pinfunction "A3_15") (pintype "input"))
    )
    (net (code "39") (name "BA1") (class "Default")
      (node (ref "CE0") (pin "24") (pinfunction "A1_24") (pintype "bidirectional"))
      (node (ref "U13") (pin "13") (pinfunction "A2_13") (pintype "input"))
    )
    (net (code "40") (name "BA2") (class "Default")
      (node (ref "CE0") (pin "25") (pinfunction "A2_25") (pintype "bidirectional"))
      (node (ref "U13") (pin "8") (pinfunction "A4_8") (pintype "input"))
    )
    (net (code "41") (name "BA3") (class "Default")
      (node (ref "CE0") (pin "26") (pinfunction "A3_26") (pintype "bidirectional"))
      (node (ref "U13") (pin "11") (pinfunction "A1_11") (pintype "input"))
    )
    (net (code "42") (name "BA4") (class "Default")
      (node (ref "CE0") (pin "27") (pinfunction "A4_27") (pintype "bidirectional"))
      (node (ref "U14") (pin "2") (pinfunction "A1_2") (pintype "input"))
    )
    (net (code "43") (name "BA5") (class "Default")
      (node (ref "CE0") (pin "28") (pinfunction "A5_28") (pintype "bidirectional"))
      (node (ref "U14") (pin "17") (pinfunction "A4_17") (pintype "input"))
    )
    (net (code "44") (name "BA6") (class "Default")
      (node (ref "CE0") (pin "29") (pinfunction "A6_29") (pintype "bidirectional"))
      (node (ref "U14") (pin "4") (pinfunction "A2_4") (pintype "input"))
    )
    (net (code "45") (name "BA7") (class "Default")
      (node (ref "CE0") (pin "30") (pinfunction "A7_30") (pintype "bidirectional"))
      (node (ref "U14") (pin "15") (pinfunction "A3_15") (pintype "input"))
    )
    (net (code "46") (name "BA8") (class "Default")
      (node (ref "CE0") (pin "31") (pinfunction "A8_31") (pintype "bidirectional"))
      (node (ref "U14") (pin "6") (pinfunction "A3_6") (pintype "input"))
    )
    (net (code "47") (name "BA9") (class "Default")
      (node (ref "CE0") (pin "32") (pinfunction "A9_32") (pintype "bidirectional"))
      (node (ref "U14") (pin "13") (pinfunction "A2_13") (pintype "input"))
    )
    (net (code "48") (name "BA10") (class "Default")
      (node (ref "CE0") (pin "33") (pinfunction "A10_33") (pintype "bidirectional"))
      (node (ref "U14") (pin "8") (pinfunction "A4_8") (pintype "input"))
    )
    (net (code "49") (name "BA11") (class "Default")
      (node (ref "CE0") (pin "34") (pinfunction "A11_34") (pintype "bidirectional"))
      (node (ref "U14") (pin "11") (pinfunction "A1_11") (pintype "input"))
    )
    (net (code "50") (name "BA12") (class "Default")
      (node (ref "CE0") (pin "35") (pinfunction "A12_35") (pintype "bidirectional"))
      (node (ref "U15") (pin "2") (pinfunction "A1_2") (pintype "input"))
    )
    (net (code "51") (name "BA13") (class "Default")
      (node (ref "CE0") (pin "36") (pinfunction "A13_36") (pintype "bidirectional"))
      (node (ref "U15") (pin "17") (pinfunction "A4_17") (pintype "input"))
    )
    (net (code "52") (name "BA14") (class "Default")
      (node (ref "CE0") (pin "37") (pinfunction "A14_37") (pintype "bidirectional"))
      (node (ref "U15") (pin "4") (pinfunction "A2_4") (pintype "input"))
    )
    (net (code "53") (name "BA15") (class "Default")
      (node (ref "CE0") (pin "38") (pinfunction "A15_38") (pintype "bidirectional"))
      (node (ref "U15") (pin "15") (pinfunction "A3_15") (pintype "input"))
    )
    (net (code "54") (name "BA16") (class "Default")
      (node (ref "CE0") (pin "39") (pinfunction "A16_39") (pintype "bidirectional"))
      (node (ref "U15") (pin "6") (pinfunction "A3_6") (pintype "input"))
    )
    (net (code "55") (name "BA17") (class "Default")
      (node (ref "CE0") (pin "40") (pinfunction "A17_40") (pintype "bidirectional"))
      (node (ref "U15") (pin "13") (pinfunction "A2_13") (pintype "input"))
    )
    (net (code "56") (name "BA18") (class "Default")
      (node (ref "CE0") (pin "41") (pinfunction "A18_41") (pintype "bidirectional"))
      (node (ref "U15") (pin "8") (pinfunction "A4_8") (pintype "input"))
    )
    (net (code "57") (name "BA19") (class "Default")
      (node (ref "CE0") (pin "42") (pinfunction "A19_42") (pintype "bidirectional"))
      (node (ref "U15") (pin "11") (pinfunction "A1_11") (pintype "input"))
    )
    (net (code "58") (name "D0") (class "Default")
      (node (ref "CF1") (pin "21") (pinfunction "D00_21") (pintype "tri_state"))
      (node (ref "RN2") (pin "2") (pinfunction "2_2") (pintype "passive"))
      (node (ref "U1") (pin "11") (pinfunction "D0_11") (pintype "tri_state"))
      (node (ref "U10") (pin "18") (pinfunction "Y1_18") (pintype "tri_state"))
      (node (ref "U16") (pin "18") (pinfunction "B1_18") (pintype "bidirectional"))
      (node (ref "U2") (pin "13") (pinfunction "D0_13") (pintype "tri_state"))
      (node (ref "U3") (pin "13") (pinfunction "D0_13") (pintype "tri_state"))
      (node (ref "U4") (pin "11") (pinfunction "D0_11") (pintype "tri_state"))
      (node (ref "U9") (pin "18") (pinfunction "Y1_18") (pintype "tri_state"))
    )
    (net (code "59") (name "D1") (class "Default")
      (node (ref "CF1") (pin "22") (pinfunction "D01_22") (pintype "tri_state"))
      (node (ref "RN2") (pin "3") (pinfunction "3_3") (pintype "passive"))
      (node (ref "U1") (pin "12") (pinfunction "D1_12") (pintype "tri_state"))
      (node (ref "U10") (pin "3") (pinfunction "Y4_3") (pintype "tri_state"))
      (node (ref "U16") (pin "17") (pinfunction "B2_17") (pintype "bidirectional"))
      (node (ref "U2") (pin "14") (pinfunction "D1_14") (pintype "tri_state"))
      (node (ref "U3") (pin "14") (pinfunction "D1_14") (pintype "tri_state"))
      (node (ref "U4") (pin "12") (pinfunction "D1_12") (pintype "tri_state"))
      (node (ref "U9") (pin "3") (pinfunction "Y4_3") (pintype "tri_state"))
    )
    (net (code "60") (name "D2") (class "Default")
      (node (ref "CF1") (pin "23") (pinfunction "D02_23") (pintype "tri_state"))
      (node (ref "RN2") (pin "4") (pinfunction "4_4") (pintype "passive"))
      (node (ref "U1") (pin "13") (pinfunction "D2_13") (pintype "tri_state"))
      (node (ref "U10") (pin "16") (pinfunction "Y2_16") (pintype "tri_state"))
      (node (ref "U16") (pin "16") (pinfunction "B3_16") (pintype "bidirectional"))
      (node (ref "U2") (pin "15") (pinfunction "D2_15") (pintype "tri_state"))
      (node (ref "U3") (pin "15") (pinfunction "D2_15") (pintype "tri_state"))
      (node (ref "U4") (pin "13") (pinfunction "D2_13") (pintype "tri_state"))
      (node (ref "U9") (pin "16") (pinfunction "Y2_16") (pintype "tri_state"))
    )
    (net (code "61") (name "D3") (class "Default")
      (node (ref "CF1") (pin "2") (pinfunction "D03_2") (pintype "tri_state"))
      (node (ref "RN2") (pin "5") (pinfunction "5_5") (pintype "passive"))
      (node (ref "U1") (pin "15") (pinfunction "D3_15") (pintype "tri_state"))
      (node (ref "U10") (pin "5") (pinfunction "Y3_5") (pintype "tri_state"))
      (node (ref "U16") (pin "15") (pinfunction "B4_15") (pintype "bidirectional"))
      (node (ref "U2") (pin "17") (pinfunction "D3_17") (pintype "tri_state"))
      (node (ref "U3") (pin "17") (pinfunction "D3_17") (pintype "tri_state"))
      (node (ref "U4") (pin "15") (pinfunction "D3_15") (pintype "tri_state"))
      (node (ref "U9") (pin "5") (pinfunction "Y3_5") (pintype "tri_state"))
    )
    (net (code "62") (name "D4") (class "Default")
      (node (ref "CF1") (pin "3") (pinfunction "D04_3") (pintype "tri_state"))
      (node (ref "RN2") (pin "6") (pinfunction "6_6") (pintype "passive"))
      (node (ref "U1") (pin "16") (pinfunction "D4_16") (pintype "tri_state"))
      (node (ref "U10") (pin "14") (pinfunction "Y3_14") (pintype "tri_state"))
      (node (ref "U16") (pin "14") (pinfunction "B5_14") (pintype "bidirectional"))
      (node (ref "U2") (pin "18") (pinfunction "D4_18") (pintype "tri_state"))
      (node (ref "U3") (pin "18") (pinfunction "D4_18") (pintype "tri_state"))
      (node (ref "U4") (pin "16") (pinfunction "D4_16") (pintype "tri_state"))
      (node (ref "U9") (pin "14") (pinfunction "Y3_14") (pintype "tri_state"))
    )
    (net (code "63") (name "D5") (class "Default")
      (node (ref "CF1") (pin "4") (pinfunction "D05_4") (pintype "tri_state"))
      (node (ref "RN2") (pin "7") (pinfunction "7_7") (pintype "passive"))
      (node (ref "U1") (pin "17") (pinfunction "D5_17") (pintype "tri_state"))
      (node (ref "U10") (pin "7") (pinfunction "Y2_7") (pintype "tri_state"))
      (node (ref "U16") (pin "13") (pinfunction "B6_13") (pintype "bidirectional"))
      (node (ref "U2") (pin "19") (pinfunction "D5_19") (pintype "tri_state"))
      (node (ref "U3") (pin "19") (pinfunction "D5_19") (pintype "tri_state"))
      (node (ref "U4") (pin "17") (pinfunction "D5_17") (pintype "tri_state"))
      (node (ref "U9") (pin "7") (pinfunction "Y2_7") (pintype "tri_state"))
    )
    (net (code "64") (name "D6") (class "Default")
      (node (ref "CF1") (pin "5") (pinfunction "D06_5") (pintype "tri_state"))
      (node (ref "RN2") (pin "8") (pinfunction "8_8") (pintype "passive"))
      (node (ref "U1") (pin "18") (pinfunction "D6_18") (pintype "tri_state"))
      (node (ref "U10") (pin "12") (pinfunction "Y4_12") (pintype "tri_state"))
      (node (ref "U16") (pin "12") (pinfunction "B7_12") (pintype "bidirectional"))
      (node (ref "U2") (pin "20") (pinfunction "D6_20") (pintype "tri_state"))
      (node (ref "U3") (pin "20") (pinfunction "D6_20") (pintype "tri_state"))
      (node (ref "U4") (pin "18") (pinfunction "D6_18") (pintype "tri_state"))
      (node (ref "U9") (pin "12") (pinfunction "Y4_12") (pintype "tri_state"))
    )
    (net (code "65") (name "D7") (class "Default")
      (node (ref "CF1") (pin "6") (pinfunction "D07_6") (pintype "tri_state"))
      (node (ref "RN2") (pin "9") (pinfunction "9_9") (pintype "passive"))
      (node (ref "U1") (pin "19") (pinfunction "D7_19") (pintype "tri_state"))
      (node (ref "U10") (pin "9") (pinfunction "Y1_9") (pintype "tri_state"))
      (node (ref "U16") (pin "11") (pinfunction "B8_11") (pintype "bidirectional"))
      (node (ref "U2") (pin "21") (pinfunction "D7_21") (pintype "tri_state"))
      (node (ref "U3") (pin "21") (pinfunction "D7_21") (pintype "tri_state"))
      (node (ref "U4") (pin "19") (pinfunction "D7_19") (pintype "tri_state"))
      (node (ref "U9") (pin "9") (pinfunction "Y1_9") (pintype "tri_state"))
    )
    (net (code "66") (name "GND") (class "Default")
      (node (ref "BT1") (pin "-") (pinfunction "-_-") (pintype "passive"))
      (node (ref "C1") (pin "2") (pinfunction "2_2") (pintype "passive"))
      (node (ref "C10") (pin "2") (pinfunction "2_2") (pintype "passive"))
      (node (ref "C11") (pin "2") (pinfunction "2_2") (pintype "passive"))
      (node (ref "C12") (pin "2") (pinfunction "2_2") (pintype "passive"))
      (node (ref "C13") (pin "2") (pinfunction "2_2") (pintype "passive"))
      (node (ref "C14") (pin "2") (pinfunction "2_2") (pintype "passive"))
      (node (ref "C15") (pin "2") (pinfunction "2_2") (pintype "passive"))
      (node (ref "C16") (pin "2") (pinfunction "2_2") (pintype "passive"))
      (node (ref "C17") (pin "2") (pinfunction "2_2") (pintype "passive"))
      (node (ref "C18") (pin "2") (pinfunction "2_2") (pintype "passive"))
      (node (ref "C19") (pin "-") (pinfunction "-_-") (pintype "passive"))
      (node (ref "C2") (pin "2") (pinfunction "2_2") (pintype "passive"))
      (node (ref "C3") (pin "2") (pinfunction "2_2") (pintype "passive"))
      (node (ref "C4") (pin "2") (pinfunction "2_2") (pintype "passive"))
      (node (ref "C5") (pin "2") (pinfunction "2_2") (pintype "passive"))
      (node (ref "C6") (pin "2") (pinfunction "2_2") (pintype "passive"))
      (node (ref "C7") (pin "2") (pinfunction "2_2") (pintype "passive"))
      (node (ref "C8") (pin "2") (pinfunction "2_2") (pintype "passive"))
      (node (ref "C9") (pin "2") (pinfunction "2_2") (pintype "passive"))
      (node (ref "CE0") (pin "3") (pinfunction "GND_3") (pintype "bidirectional"))
      (node (ref "CE0") (pin "4") (pinfunction "GND_4") (pintype "bidirectional"))
      (node (ref "CE0") (pin "62") (pinfunction "GND_62") (pintype "bidirectional"))
      (node (ref "CF1") (pin "10") (pinfunction "A09_10") (pintype "input"))
      (node (ref "CF1") (pin "11") (pinfunction "A08_11") (pintype "input"))
      (node (ref "CF1") (pin "12") (pinfunction "A07_12") (pintype "input"))
      (node (ref "CF1") (pin "14") (pinfunction "A06_14") (pintype "input"))
      (node (ref "CF1") (pin "15") (pinfunction "A05_15") (pintype "input"))
      (node (ref "CF1") (pin "16") (pinfunction "A04_16") (pintype "input"))
      (node (ref "CF1") (pin "17") (pinfunction "A03_17") (pintype "input"))
      (node (ref "CF1") (pin "39") (pinfunction "~{CSEL}_39") (pintype "input"))
      (node (ref "CF1") (pin "8") (pinfunction "A10_8") (pintype "input"))
      (node (ref "CF1") (pin "9") (pinfunction "~{ATASEL}_9") (pintype "input"))
      (node (ref "D1") (pin "K") (pinfunction "C_K") (pintype "passive"))
      (node (ref "R10") (pin "1") (pinfunction "1_1") (pintype "passive"))
      (node (ref "R7") (pin "1") (pinfunction "1_1") (pintype "passive"))
      (node (ref "R8") (pin "1") (pinfunction "1_1") (pintype "passive"))
      (node (ref "R9") (pin "1") (pinfunction "1_1") (pintype "passive"))
      (node (ref "RN1") (pin "1") (pinfunction "1_1") (pintype "passive"))
      (node (ref "U13") (pin "1") (pinfunction "G_1") (pintype "input"))
      (node (ref "U13") (pin "19") (pinfunction "G_19") (pintype "input"))
      (node (ref "U14") (pin "1") (pinfunction "G_1") (pintype "input"))
      (node (ref "U14") (pin "19") (pinfunction "G_19") (pintype "input"))
      (node (ref "U15") (pin "1") (pinfunction "G_1") (pintype "input"))
      (node (ref "U15") (pin "19") (pinfunction "G_19") (pintype "input"))
      (node (ref "U2") (pin "16") (pinfunction "GND_16") (pintype "power_in"))
    )
    (net (code "67") (name "ID0") (class "Default")
      (node (ref "U10") (pin "2") (pinfunction "A1_2") (pintype "input"))
    )
    (net (code "68") (name "ID1") (class "Default")
      (node (ref "U10") (pin "17") (pinfunction "A4_17") (pintype "input"))
    )
    (net (code "69") (name "ID2") (class "Default")
      (node (ref "U10") (pin "4") (pinfunction "A2_4") (pintype "input"))
    )
    (net (code "70") (name "ID3") (class "Default")
      (node (ref "U10") (pin "15") (pinfunction "A3_15") (pintype "input"))
    )
    (net (code "71") (name "ID4") (class "Default")
      (node (ref "U10") (pin "6") (pinfunction "A3_6") (pintype "input"))
    )
    (net (code "72") (name "ID5") (class "Default")
      (node (ref "U10") (pin "13") (pinfunction "A2_13") (pintype "input"))
    )
    (net (code "73") (name "ID6") (class "Default")
      (node (ref "U10") (pin "8") (pinfunction "A4_8") (pintype "input"))
    )
    (net (code "74") (name "ID7") (class "Default")
      (node (ref "U10") (pin "11") (pinfunction "A1_11") (pintype "input"))
    )
    (net (code "75") (name "INT_CF") (class "Default")
      (node (ref "CF1") (pin "37") (pinfunction "INTRQ_37") (pintype "output"))
      (node (ref "JP5") (pin "1") (pinfunction "1_1") (pintype "passive"))
    )
    (net (code "76") (name "Net-(CE0-D0)") (class "Default")
      (node (ref "CE0") (pin "43") (pinfunction "D0_43") (pintype "bidirectional"))
      (node (ref "U16") (pin "2") (pinfunction "A1_2") (pintype "bidirectional"))
    )
    (net (code "77") (name "Net-(CE0-D1)") (class "Default")
      (node (ref "CE0") (pin "44") (pinfunction "D1_44") (pintype "bidirectional"))
      (node (ref "U16") (pin "3") (pinfunction "A2_3") (pintype "bidirectional"))
    )
    (net (code "78") (name "Net-(CE0-D2)") (class "Default")
      (node (ref "CE0") (pin "45") (pinfunction "D2_45") (pintype "bidirectional"))
      (node (ref "U16") (pin "4") (pinfunction "A3_4") (pintype "bidirectional"))
    )
    (net (code "79") (name "Net-(CE0-D3)") (class "Default")
      (node (ref "CE0") (pin "46") (pinfunction "D3_46") (pintype "bidirectional"))
      (node (ref "U16") (pin "5") (pinfunction "A4_5") (pintype "bidirectional"))
    )
    (net (code "80") (name "Net-(CE0-D4)") (class "Default")
      (node (ref "CE0") (pin "47") (pinfunction "D4_47") (pintype "bidirectional"))
      (node (ref "U16") (pin "6") (pinfunction "A5_6") (pintype "bidirectional"))
    )
    (net (code "81") (name "Net-(CE0-D5)") (class "Default")
      (node (ref "CE0") (pin "48") (pinfunction "D5_48") (pintype "bidirectional"))
      (node (ref "U16") (pin "7") (pinfunction "A6_7") (pintype "bidirectional"))
    )
    (net (code "82") (name "Net-(CE0-D6)") (class "Default")
      (node (ref "CE0") (pin "49") (pinfunction "D6_49") (pintype "bidirectional"))
      (node (ref "U16") (pin "8") (pinfunction "A7_8") (pintype "bidirectional"))
    )
    (net (code "83") (name "Net-(CE0-D7)") (class "Default")
      (node (ref "CE0") (pin "50") (pinfunction "D7_50") (pintype "bidirectional"))
      (node (ref "U16") (pin "9") (pinfunction "A8_9") (pintype "bidirectional"))
    )
    (net (code "84") (name "Net-(CF1A-IORDY)") (class "Default")
      (node (ref "CF1") (pin "42") (pinfunction "IORDY_42") (pintype "output"))
      (node (ref "JP4") (pin "2") (pinfunction "2_2") (pintype "passive"))
    )
    (net (code "85") (name "Net-(CF1A-~{DASP})") (class "Default")
      (node (ref "CF1") (pin "45") (pinfunction "~{DASP}_45") (pintype "open_collector"))
      (node (ref "D2") (pin "C") (pinfunction "C_C") (pintype "passive"))
    )
    (net (code "86") (name "Net-(CF1A-~{PDIAG})") (class "Default")
      (node (ref "CF1") (pin "46") (pinfunction "~{PDIAG}_46") (pintype "output"))
      (node (ref "R12") (pin "1") (pinfunction "1_1") (pintype "passive"))
    )
    (net (code "87") (name "Net-(D1-PadA)") (class "Default")
      (node (ref "D1") (pin "A") (pinfunction "A_A") (pintype "passive"))
      (node (ref "R1") (pin "1") (pinfunction "1_1") (pintype "passive"))
    )
    (net (code "88") (name "Net-(D2-PadA)") (class "Default")
      (node (ref "D2") (pin "A") (pinfunction "A_A") (pintype "passive"))
      (node (ref "R11") (pin "1") (pinfunction "1_1") (pintype "passive"))
    )
    (net (code "89") (name "Net-(JP8-Pad1)") (class "Default")
      (node (ref "JP8") (pin "1") (pinfunction "1_1") (pintype "passive"))
      (node (ref "R8") (pin "2") (pinfunction "2_2") (pintype "passive"))
      (node (ref "S2") (pin "3") (pinfunction "3_3") (pintype "passive"))
    )
    (net (code "90") (name "Net-(JP10-Pad1)") (class "Default")
      (node (ref "JP10") (pin "1") (pinfunction "1_1") (pintype "passive"))
      (node (ref "R9") (pin "2") (pinfunction "2_2") (pintype "passive"))
      (node (ref "S2") (pin "2") (pinfunction "2_2") (pintype "passive"))
    )
    (net (code "91") (name "Net-(JP12-Pad1)") (class "Default")
      (node (ref "JP12") (pin "1") (pinfunction "1_1") (pintype "passive"))
      (node (ref "R10") (pin "2") (pinfunction "2_2") (pintype "passive"))
      (node (ref "S2") (pin "1") (pinfunction "1_1") (pintype "passive"))
    )
    (net (code "92") (name "Net-(Q1-B)") (class "Default")
      (node (ref "Q1") (pin "2") (pinfunction "B_2") (pintype "passive"))
      (node (ref "R2") (pin "2") (pinfunction "2_2") (pintype "passive"))
    )
    (net (code "93") (name "Net-(Q1-C)") (class "Default")
      (node (ref "Q1") (pin "3") (pinfunction "C_3") (pintype "passive"))
      (node (ref "R1") (pin "2") (pinfunction "2_2") (pintype "passive"))
    )
    (net (code "94") (name "Net-(U1A-A12)") (class "Default")
      (node (ref "JP8") (pin "2") (pinfunction "2_2") (pintype "passive"))
      (node (ref "U1") (pin "2") (pinfunction "A12_2") (pintype "input"))
    )
    (net (code "95") (name "Net-(U1A-A13)") (class "Default")
      (node (ref "JP10") (pin "2") (pinfunction "2_2") (pintype "passive"))
      (node (ref "U1") (pin "26") (pinfunction "A13_26") (pintype "input"))
    )
    (net (code "96") (name "Net-(U1A-A14)") (class "Default")
      (node (ref "JP12") (pin "2") (pinfunction "2_2") (pintype "passive"))
      (node (ref "U1") (pin "1") (pinfunction "A14_1") (pintype "input"))
    )
    (net (code "97") (name "Net-(U2A-~{CE})") (class "Default")
      (node (ref "JP6") (pin "2") (pinfunction "2_2") (pintype "passive"))
      (node (ref "U2") (pin "22") (pinfunction "~{CE}_22") (pintype "input"))
    )
    (net (code "98") (name "Net-(U2B-VCC)") (class "Default")
      (node (ref "C2") (pin "1") (pinfunction "1_1") (pintype "passive"))
      (node (ref "JP7") (pin "2") (pinfunction "2_2") (pintype "passive"))
      (node (ref "U2") (pin "32") (pinfunction "VCC_32") (pintype "power_in"))
    )
    (net (code "99") (name "Net-(U3A-~{CE})") (class "Default")
      (node (ref "U3") (pin "22") (pinfunction "~{CE}_22") (pintype "input"))
      (node (ref "U7") (pin "6") (pinfunction "O_6") (pintype "output"))
    )
    (net (code "100") (name "Net-(U4A-BC)") (class "Default")
      (node (ref "BT1") (pin "+") (pinfunction "+_+") (pintype "passive"))
      (node (ref "U4") (pin "24") (pinfunction "BC_24") (pintype "input"))
    )
    (net (code "101") (name "Net-(U4A-VCC)") (class "Default")
      (node (ref "C4") (pin "1") (pinfunction "1_1") (pintype "passive"))
      (node (ref "JP14") (pin "2") (pinfunction "2_2") (pintype "passive"))
      (node (ref "U4") (pin "28") (pinfunction "VCC_28") (pintype "input"))
    )
    (net (code "102") (name "Net-(U4A-WDI)") (class "Default")
      (node (ref "JP1") (pin "2") (pinfunction "2_2") (pintype "passive"))
      (node (ref "U4") (pin "23") (pinfunction "WDI_23") (pintype "input"))
    )
    (net (code "103") (name "Net-(U4A-X1)") (class "Default")
      (node (ref "U4") (pin "2") (pinfunction "X1_2") (pintype "input"))
      (node (ref "Y1") (pin "2") (pinfunction "2_2") (pintype "passive"))
    )
    (net (code "104") (name "Net-(U4A-X2)") (class "Default")
      (node (ref "U4") (pin "3") (pinfunction "X2_3") (pintype "input"))
      (node (ref "Y1") (pin "1") (pinfunction "1_1") (pintype "passive"))
    )
    (net (code "105") (name "Net-(U4A-~{RST})") (class "Default")
      (node (ref "JP2") (pin "1") (pinfunction "1_1") (pintype "passive"))
      (node (ref "U4") (pin "6") (pinfunction "~{RST}_6") (pintype "open_collector"))
    )
    (net (code "106") (name "Net-(U4A-~{WDO})") (class "Default")
      (node (ref "R2") (pin "1") (pinfunction "1_1") (pintype "passive"))
      (node (ref "U4") (pin "4") (pinfunction "~{WDO}_4") (pintype "output"))
    )
    (net (code "107") (name "Net-(U5A-G)") (class "Default")
      (node (ref "U5") (pin "1") (pinfunction "G_1") (pintype "input"))
      (node (ref "U8") (pin "2") (pinfunction "O_2") (pintype "output"))
    )
    (net (code "108") (name "Net-(U5A-P0)") (class "Default")
      (node (ref "JP9") (pin "2") (pinfunction "2_2") (pintype "passive"))
      (node (ref "U5") (pin "2") (pinfunction "P0_2") (pintype "input"))
    )
    (net (code "109") (name "Net-(U5A-P1)") (class "Default")
      (node (ref "JP13") (pin "2") (pinfunction "2_2") (pintype "passive"))
      (node (ref "U5") (pin "4") (pinfunction "P1_4") (pintype "input"))
    )
    (net (code "110") (name "Net-(U5A-P7)") (class "Default")
      (node (ref "JP11") (pin "2") (pinfunction "2_2") (pintype "passive"))
      (node (ref "U5") (pin "17") (pinfunction "P7_17") (pintype "input"))
    )
    (net (code "111") (name "Net-(U6A-I0)") (class "Default")
      (node (ref "U6") (pin "1") (pinfunction "I0_1") (pintype "input"))
      (node (ref "U8") (pin "12") (pinfunction "O_12") (pintype "output"))
    )
    (net (code "112") (name "Net-(U7A-I0)") (class "Default")
      (node (ref "U7") (pin "1") (pinfunction "I0_1") (pintype "input"))
      (node (ref "U8") (pin "6") (pinfunction "O_6") (pintype "output"))
    )
    (net (code "113") (name "Net-(U7C-O)") (class "Default")
      (node (ref "U7") (pin "8") (pinfunction "O_8") (pintype "output"))
      (node (ref "U8") (pin "9") (pinfunction "I_9") (pintype "input"))
    )
    (net (code "114") (name "Net-(U8B-I)") (class "Default")
      (node (ref "JP5") (pin "2") (pinfunction "2_2") (pintype "passive"))
      (node (ref "R7") (pin "2") (pinfunction "2_2") (pintype "passive"))
      (node (ref "U8") (pin "3") (pinfunction "I_3") (pintype "input"))
    )
    (net (code "115") (name "Net-(U16A-G)") (class "Default")
      (node (ref "U16") (pin "19") (pinfunction "G_19") (pintype "input"))
      (node (ref "U6") (pin "3") (pinfunction "O_3") (pintype "output"))
    )
    (net (code "116") (name "SW12") (class "Default")
      (node (ref "JP9") (pin "3") (pinfunction "3_3") (pintype "passive"))
      (node (ref "RN1") (pin "2") (pinfunction "2_2") (pintype "passive"))
      (node (ref "S1") (pin "8") (pinfunction "8_8") (pintype "passive"))
      (node (ref "U5") (pin "3") (pinfunction "Q0_3") (pintype "input"))
    )
    (net (code "117") (name "SW13") (class "Default")
      (node (ref "JP11") (pin "3") (pinfunction "3_3") (pintype "passive"))
      (node (ref "RN1") (pin "3") (pinfunction "3_3") (pintype "passive"))
      (node (ref "S1") (pin "7") (pinfunction "7_7") (pintype "passive"))
      (node (ref "U5") (pin "18") (pinfunction "Q7_18") (pintype "input"))
    )
    (net (code "118") (name "SW14") (class "Default")
      (node (ref "JP13") (pin "3") (pinfunction "3_3") (pintype "passive"))
      (node (ref "RN1") (pin "4") (pinfunction "4_4") (pintype "passive"))
      (node (ref "S1") (pin "6") (pinfunction "6_6") (pintype "passive"))
      (node (ref "U5") (pin "5") (pinfunction "Q1_5") (pintype "input"))
    )
    (net (code "119") (name "SW15") (class "Default")
      (node (ref "RN1") (pin "5") (pinfunction "5_5") (pintype "passive"))
      (node (ref "S1") (pin "5") (pinfunction "5_5") (pintype "passive"))
      (node (ref "U5") (pin "16") (pinfunction "Q6_16") (pintype "input"))
    )
    (net (code "120") (name "SW16") (class "Default")
      (node (ref "RN1") (pin "6") (pinfunction "6_6") (pintype "passive"))
      (node (ref "S1") (pin "4") (pinfunction "4_4") (pintype "passive"))
      (node (ref "U5") (pin "7") (pinfunction "Q2_7") (pintype "input"))
    )
    (net (code "121") (name "SW17") (class "Default")
      (node (ref "RN1") (pin "7") (pinfunction "7_7") (pintype "passive"))
      (node (ref "S1") (pin "3") (pinfunction "3_3") (pintype "passive"))
      (node (ref "U5") (pin "14") (pinfunction "Q5_14") (pintype "input"))
    )
    (net (code "122") (name "SW18") (class "Default")
      (node (ref "RN1") (pin "8") (pinfunction "8_8") (pintype "passive"))
      (node (ref "S1") (pin "2") (pinfunction "2_2") (pintype "passive"))
      (node (ref "U5") (pin "9") (pinfunction "Q3_9") (pintype "input"))
    )
    (net (code "123") (name "SW19") (class "Default")
      (node (ref "RN1") (pin "9") (pinfunction "9_9") (pintype "passive"))
      (node (ref "S1") (pin "1") (pinfunction "1_1") (pintype "passive"))
      (node (ref "U5") (pin "12") (pinfunction "Q4_12") (pintype "input"))
    )
    (net (code "124") (name "VBAT") (class "Default")
      (node (ref "JP7") (pin "3") (pinfunction "3_3") (pintype "passive"))
      (node (ref "U4") (pin "1") (pinfunction "VOUT_1") (pintype "input"))
    )
    (net (code "125") (name "VCC") (class "Default")
      (node (ref "C1") (pin "1") (pinfunction "1_1") (pintype "passive"))
      (node (ref "C10") (pin "1") (pinfunction "1_1") (pintype "passive"))
      (node (ref "C11") (pin "1") (pinfunction "1_1") (pintype "passive"))
      (node (ref "C12") (pin "1") (pinfunction "1_1") (pintype "passive"))
      (node (ref "C13") (pin "1") (pinfunction "1_1") (pintype "passive"))
      (node (ref "C14") (pin "1") (pinfunction "1_1") (pintype "passive"))
      (node (ref "C15") (pin "1") (pinfunction "1_1") (pintype "passive"))
      (node (ref "C16") (pin "1") (pinfunction "1_1") (pintype "passive"))
      (node (ref "C17") (pin "1") (pinfunction "1_1") (pintype "passive"))
      (node (ref "C18") (pin "1") (pinfunction "1_1") (pintype "passive"))
      (node (ref "C19") (pin "+") (pinfunction "+_+") (pintype "passive"))
      (node (ref "C3") (pin "1") (pinfunction "1_1") (pintype "passive"))
      (node (ref "C5") (pin "1") (pinfunction "1_1") (pintype "passive"))
      (node (ref "C6") (pin "1") (pinfunction "1_1") (pintype "passive"))
      (node (ref "C7") (pin "1") (pinfunction "1_1") (pintype "passive"))
      (node (ref "C8") (pin "1") (pinfunction "1_1") (pintype "passive"))
      (node (ref "C9") (pin "1") (pinfunction "1_1") (pintype "passive"))
      (node (ref "CE0") (pin "5") (pinfunction "+5V_5") (pintype "bidirectional"))
      (node (ref "CE0") (pin "6") (pinfunction "+5V_6") (pintype "bidirectional"))
      (node (ref "CF1") (pin "32") (pinfunction "~{CS1}_32") (pintype "input"))
      (node (ref "CF1") (pin "36") (pinfunction "~{WE}_36") (pintype "input"))
      (node (ref "CF1") (pin "44") (pinfunction "~{DMACK}_44") (pintype "input"))
      (node (ref "JP14") (pin "3") (pinfunction "3_3") (pintype "passive"))
      (node (ref "JP7") (pin "1") (pinfunction "1_1") (pintype "passive"))
      (node (ref "Q1") (pin "1") (pinfunction "E_1") (pintype "passive"))
      (node (ref "R11") (pin "2") (pinfunction "2_2") (pintype "passive"))
      (node (ref "R12") (pin "2") (pinfunction "2_2") (pintype "passive"))
      (node (ref "R3") (pin "1") (pinfunction "1_1") (pintype "passive"))
      (node (ref "R4") (pin "2") (pinfunction "2_2") (pintype "passive"))
      (node (ref "R5") (pin "1") (pinfunction "1_1") (pintype "passive"))
      (node (ref "R6") (pin "1") (pinfunction "1_1") (pintype "passive"))
      (node (ref "RN2") (pin "1") (pinfunction "1_1") (pintype "passive"))
      (node (ref "S1") (pin "10") (pinfunction "10_10") (pintype "passive"))
      (node (ref "S1") (pin "11") (pinfunction "11_11") (pintype "passive"))
      (node (ref "S1") (pin "12") (pinfunction "12_12") (pintype "passive"))
      (node (ref "S1") (pin "13") (pinfunction "13_13") (pintype "passive"))
      (node (ref "S1") (pin "14") (pinfunction "14_14") (pintype "passive"))
      (node (ref "S1") (pin "15") (pinfunction "15_15") (pintype "passive"))
      (node (ref "S1") (pin "16") (pinfunction "16_16") (pintype "passive"))
      (node (ref "S1") (pin "9") (pinfunction "9_9") (pintype "passive"))
      (node (ref "S2") (pin "4") (pinfunction "4_4") (pintype "passive"))
      (node (ref "S2") (pin "5") (pinfunction "5_5") (pintype "passive"))
      (node (ref "S2") (pin "6") (pinfunction "6_6") (pintype "passive"))
      (node (ref "U1") (pin "27") (pinfunction "~{WE}_27") (pintype "input"))
      (node (ref "U11") (pin "6") (pinfunction "G1_6") (pintype "input"))
      (node (ref "U13") (pin "2") (pinfunction "A1_2") (pintype "input"))
      (node (ref "U6") (pin "10") (pinfunction "I1_10") (pintype "input"))
      (node (ref "U6") (pin "12") (pinfunction "I0_12") (pintype "input"))
      (node (ref "U6") (pin "13") (pinfunction "I1_13") (pintype "input"))
      (node (ref "U6") (pin "4") (pinfunction "I0_4") (pintype "input"))
      (node (ref "U6") (pin "5") (pinfunction "I1_5") (pintype "input"))
      (node (ref "U6") (pin "9") (pinfunction "I0_9") (pintype "input"))
      (node (ref "U7") (pin "9") (pinfunction "I0_9") (pintype "input"))
      (node (ref "U8") (pin "11") (pinfunction "I_11") (pintype "input"))
      (node (ref "U9") (pin "11") (pinfunction "A1_11") (pintype "input"))
      (node (ref "U9") (pin "13") (pinfunction "A2_13") (pintype "input"))
      (node (ref "U9") (pin "6") (pinfunction "A3_6") (pintype "input"))
      (node (ref "U9") (pin "8") (pinfunction "A4_8") (pintype "input"))
    )
    (net (code "126") (name "unconnected-(CE0-+3.3V-Pad2)") (class "Default")
      (node (ref "CE0") (pin "2") (pinfunction "+3.3V_2") (pintype "bidirectional"))
    )
    (net (code "127") (name "unconnected-(CE0-+12V-Pad1)") (class "Default")
      (node (ref "CE0") (pin "1") (pinfunction "+12V_1") (pintype "bidirectional"))
    )
    (net (code "128") (name "unconnected-(CE0--12V-Pad7)") (class "Default")
      (node (ref "CE0") (pin "7") (pinfunction "-12V_7") (pintype "bidirectional"))
    )
    (net (code "129") (name "unconnected-(CE0-CLK-Pad15)") (class "Default")
      (node (ref "CE0") (pin "15") (pinfunction "CLK_15") (pintype "bidirectional"))
    )
    (net (code "130") (name "unconnected-(CE0-CLKAUX-Pad16)") (class "Default")
      (node (ref "CE0") (pin "16") (pinfunction "CLKAUX_16") (pintype "bidirectional"))
    )
    (net (code "131") (name "unconnected-(CE0-~{BUSACK}-Pad20)") (class "Default")
      (node (ref "CE0") (pin "20") (pinfunction "~{BUSACK}_20") (pintype "bidirectional"))
    )
    (net (code "132") (name "unconnected-(CE0-~{BUSRQ}-Pad10)") (class "Default")
      (node (ref "CE0") (pin "10") (pinfunction "~{BUSRQ}_10") (pintype "bidirectional"))
    )
    (net (code "133") (name "unconnected-(CE0-~{CBR}-Pad12)") (class "Default")
      (node (ref "CE0") (pin "12") (pinfunction "~{CBR}_12") (pintype "bidirectional"))
    )
    (net (code "134") (name "unconnected-(CE0-~{FETCH}-Pad19)") (class "Default")
      (node (ref "CE0") (pin "19") (pinfunction "~{FETCH}_19") (pintype "bidirectional"))
    )
    (net (code "135") (name "unconnected-(CE0-~{HALT}-Pad17)") (class "Default")
      (node (ref "CE0") (pin "17") (pinfunction "~{HALT}_17") (pintype "bidirectional"))
    )
    (net (code "136") (name "unconnected-(CE0-~{INH}-Pad11)") (class "Default")
      (node (ref "CE0") (pin "11") (pinfunction "~{INH}_11") (pintype "bidirectional"))
    )
    (net (code "137") (name "unconnected-(CE0-~{INT}-Pad51)") (class "Default")
      (node (ref "CE0") (pin "51") (pinfunction "~{INT}_51") (pintype "bidirectional"))
    )
    (net (code "138") (name "unconnected-(CE0-~{IRQ0}-Pad53)") (class "Default")
      (node (ref "CE0") (pin "53") (pinfunction "~{IRQ0}_53") (pintype "bidirectional"))
    )
    (net (code "139") (name "unconnected-(CE0-~{IRQ1}-Pad54)") (class "Default")
      (node (ref "CE0") (pin "54") (pinfunction "~{IRQ1}_54") (pintype "bidirectional"))
    )
    (net (code "140") (name "unconnected-(CE0-~{IRQ2}-Pad55)") (class "Default")
      (node (ref "CE0") (pin "55") (pinfunction "~{IRQ2}_55") (pintype "bidirectional"))
    )
    (net (code "141") (name "unconnected-(CE0-~{IRQ3}-Pad56)") (class "Default")
      (node (ref "CE0") (pin "56") (pinfunction "~{IRQ3}_56") (pintype "bidirectional"))
    )
    (net (code "142") (name "unconnected-(CE0-~{IRQ4}-Pad57)") (class "Default")
      (node (ref "CE0") (pin "57") (pinfunction "~{IRQ4}_57") (pintype "bidirectional"))
    )
    (net (code "143") (name "unconnected-(CE0-~{IRQ5}-Pad58)") (class "Default")
      (node (ref "CE0") (pin "58") (pinfunction "~{IRQ5}_58") (pintype "bidirectional"))
    )
    (net (code "144") (name "unconnected-(CE0-~{IRQ6}-Pad59)") (class "Default")
      (node (ref "CE0") (pin "59") (pinfunction "~{IRQ6}_59") (pintype "bidirectional"))
    )
    (net (code "145") (name "unconnected-(CE0-~{IRQ7}-Pad60)") (class "Default")
      (node (ref "CE0") (pin "60") (pinfunction "~{IRQ7}_60") (pintype "bidirectional"))
    )
    (net (code "146") (name "unconnected-(CE0-~{NMI}-Pad61)") (class "Default")
      (node (ref "CE0") (pin "61") (pinfunction "~{NMI}_61") (pintype "bidirectional"))
    )
    (net (code "147") (name "unconnected-(CF1A-D08-Pad47)") (class "Default")
      (node (ref "CF1") (pin "47") (pinfunction "D08_47") (pintype "tri_state"))
    )
    (net (code "148") (name "unconnected-(CF1A-D09-Pad48)") (class "Default")
      (node (ref "CF1") (pin "48") (pinfunction "D09_48") (pintype "tri_state"))
    )
    (net (code "149") (name "unconnected-(CF1A-D10-Pad49)") (class "Default")
      (node (ref "CF1") (pin "49") (pinfunction "D10_49") (pintype "tri_state"))
    )
    (net (code "150") (name "unconnected-(CF1A-D11-Pad27)") (class "Default")
      (node (ref "CF1") (pin "27") (pinfunction "D11_27") (pintype "tri_state"))
    )
    (net (code "151") (name "unconnected-(CF1A-D12-Pad28)") (class "Default")
      (node (ref "CF1") (pin "28") (pinfunction "D12_28") (pintype "tri_state"))
    )
    (net (code "152") (name "unconnected-(CF1A-D13-Pad29)") (class "Default")
      (node (ref "CF1") (pin "29") (pinfunction "D13_29") (pintype "tri_state"))
    )
    (net (code "153") (name "unconnected-(CF1A-D14-Pad30)") (class "Default")
      (node (ref "CF1") (pin "30") (pinfunction "D14_30") (pintype "tri_state"))
    )
    (net (code "154") (name "unconnected-(CF1A-D15-Pad31)") (class "Default")
      (node (ref "CF1") (pin "31") (pinfunction "D15_31") (pintype "tri_state"))
    )
    (net (code "155") (name "unconnected-(CF1A-DMARQ-Pad43)") (class "Default")
      (node (ref "CF1") (pin "43") (pinfunction "DMARQ_43") (pintype "output"))
    )
    (net (code "156") (name "unconnected-(CF1A-~{IOCS16}-Pad24)") (class "Default")
      (node (ref "CF1") (pin "24") (pinfunction "~{IOCS16}_24") (pintype "output"))
    )
    (net (code "157") (name "unconnected-(CF1A-~{VS1}-Pad33)") (class "Default")
      (node (ref "CF1") (pin "33") (pinfunction "~{VS1}_33") (pintype "output"))
    )
    (net (code "158") (name "unconnected-(CF1A-~{VS2}-Pad40)") (class "Default")
      (node (ref "CF1") (pin "40") (pinfunction "~{VS2}_40") (pintype "output"))
    )
    (net (code "159") (name "unconnected-(U6B-O-Pad6)") (class "Default")
      (node (ref "U6") (pin "6") (pinfunction "O_6") (pintype "output"))
    )
    (net (code "160") (name "unconnected-(U6C-O-Pad8)") (class "Default")
      (node (ref "U6") (pin "8") (pinfunction "O_8") (pintype "output"))
    )
    (net (code "161") (name "unconnected-(U6D-O-Pad11)") (class "Default")
      (node (ref "U6") (pin "11") (pinfunction "O_11") (pintype "output"))
    )
    (net (code "162") (name "unconnected-(U8E-O-Pad10)") (class "Default")
      (node (ref "U8") (pin "10") (pinfunction "O_10") (pintype "output"))
    )
    (net (code "163") (name "unconnected-(U11A-Y2-Pad13)") (class "Default")
      (node (ref "U11") (pin "13") (pinfunction "Y2_13") (pintype "output"))
    )
    (net (code "164") (name "unconnected-(U11A-Y3-Pad12)") (class "Default")
      (node (ref "U11") (pin "12") (pinfunction "Y3_12") (pintype "output"))
    )
    (net (code "165") (name "unconnected-(U11A-Y4-Pad11)") (class "Default")
      (node (ref "U11") (pin "11") (pinfunction "Y4_11") (pintype "output"))
    )
    (net (code "166") (name "unconnected-(U11A-Y5-Pad10)") (class "Default")
      (node (ref "U11") (pin "10") (pinfunction "Y5_10") (pintype "output"))
    )
    (net (code "167") (name "unconnected-(U11A-Y6-Pad9)") (class "Default")
      (node (ref "U11") (pin "9") (pinfunction "Y6_9") (pintype "output"))
    )
    (net (code "168") (name "unconnected-(U11A-Y7-Pad7)") (class "Default")
      (node (ref "U11") (pin "7") (pinfunction "Y7_7") (pintype "output"))
    )
    (net (code "169") (name "unconnected-(U12A-Y0-Pad15)") (class "Default")
      (node (ref "U12") (pin "15") (pinfunction "Y0_15") (pintype "output"))
    )
    (net (code "170") (name "unconnected-(U12A-Y1-Pad14)") (class "Default")
      (node (ref "U12") (pin "14") (pinfunction "Y1_14") (pintype "output"))
    )
    (net (code "171") (name "unconnected-(U12A-Y2-Pad13)") (class "Default")
      (node (ref "U12") (pin "13") (pinfunction "Y2_13") (pintype "output"))
    )
    (net (code "172") (name "unconnected-(U12A-Y3-Pad12)") (class "Default")
      (node (ref "U12") (pin "12") (pinfunction "Y3_12") (pintype "output"))
    )
    (net (code "173") (name "unconnected-(U12A-Y5-Pad10)") (class "Default")
      (node (ref "U12") (pin "10") (pinfunction "Y5_10") (pintype "output"))
    )
    (net (code "174") (name "unconnected-(U12A-Y6-Pad9)") (class "Default")
      (node (ref "U12") (pin "9") (pinfunction "Y6_9") (pintype "output"))
    )
    (net (code "175") (name "unconnected-(U13A-Y1-Pad18)") (class "Default")
      (node (ref "U13") (pin "18") (pinfunction "Y1_18") (pintype "tri_state"))
    )
    (net (code "176") (name "~{BCSX}") (class "Default")
      (node (ref "CE0") (pin "9") (pinfunction "~{CSX}_9") (pintype "bidirectional"))
      (node (ref "U13") (pin "17") (pinfunction "A4_17") (pintype "input"))
    )
    (net (code "177") (name "~{BRD}") (class "Default")
      (node (ref "CE0") (pin "21") (pinfunction "~{RD}_21") (pintype "bidirectional"))
      (node (ref "U13") (pin "4") (pinfunction "A2_4") (pintype "input"))
    )
    (net (code "178") (name "~{BWR}") (class "Default")
      (node (ref "CE0") (pin "22") (pinfunction "~{WR}_22") (pintype "bidirectional"))
      (node (ref "U13") (pin "6") (pinfunction "A3_6") (pintype "input"))
    )
    (net (code "179") (name "~{CESB}IN") (class "Default")
      (node (ref "JP6") (pin "1") (pinfunction "1_1") (pintype "passive"))
      (node (ref "U4") (pin "26") (pinfunction "~{CEIN}_26") (pintype "input"))
      (node (ref "U7") (pin "12") (pinfunction "O_12") (pintype "output"))
    )
    (net (code "180") (name "~{CESB}OUT") (class "Default")
      (node (ref "JP6") (pin "3") (pinfunction "3_3") (pintype "passive"))
      (node (ref "U4") (pin "25") (pinfunction "~{CEOUT}_25") (pintype "output"))
    )
    (net (code "181") (name "~{CF_CD1}") (class "Default")
      (node (ref "CF1") (pin "26") (pinfunction "~{CD1}_26") (pintype "output"))
      (node (ref "R6") (pin "2") (pinfunction "2_2") (pintype "passive"))
      (node (ref "U9") (pin "4") (pinfunction "A2_4") (pintype "input"))
    )
    (net (code "182") (name "~{CF_CD2}") (class "Default")
      (node (ref "CF1") (pin "25") (pinfunction "~{CD2}_25") (pintype "output"))
      (node (ref "R5") (pin "2") (pinfunction "2_2") (pintype "passive"))
      (node (ref "U9") (pin "15") (pinfunction "A3_15") (pintype "input"))
    )
    (net (code "183") (name "~{CINH}") (class "Default")
      (node (ref "CE0") (pin "13") (pinfunction "~{CINH}_13") (pintype "bidirectional"))
      (node (ref "U7") (pin "13") (pinfunction "I2_13") (pintype "input"))
      (node (ref "U7") (pin "5") (pinfunction "I2_5") (pintype "input"))
      (node (ref "U8") (pin "1") (pinfunction "I_1") (pintype "input"))
      (node (ref "U8") (pin "13") (pinfunction "I_13") (pintype "input"))
    )
    (net (code "184") (name "~{CSX}") (class "Default")
      (node (ref "U11") (pin "4") (pinfunction "G2A_4") (pintype "input"))
      (node (ref "U12") (pin "4") (pinfunction "G2A_4") (pintype "input"))
      (node (ref "U13") (pin "3") (pinfunction "Y4_3") (pintype "tri_state"))
      (node (ref "U6") (pin "2") (pinfunction "I1_2") (pintype "input"))
    )
    (net (code "185") (name "~{CS_CF}") (class "Default")
      (node (ref "CF1") (pin "7") (pinfunction "~{CS0}_7") (pintype "input"))
      (node (ref "U11") (pin "15") (pinfunction "Y0_15") (pintype "output"))
    )
    (net (code "186") (name "~{CS_ID}") (class "Default")
      (node (ref "U10") (pin "1") (pinfunction "G_1") (pintype "input"))
      (node (ref "U10") (pin "19") (pinfunction "G_19") (pintype "input"))
      (node (ref "U12") (pin "7") (pinfunction "Y7_7") (pintype "output"))
    )
    (net (code "187") (name "~{CS_RTC}") (class "Default")
      (node (ref "U11") (pin "14") (pinfunction "Y1_14") (pintype "output"))
      (node (ref "U4") (pin "21") (pinfunction "~{CS}_21") (pintype "input"))
    )
    (net (code "188") (name "~{CS_SR}") (class "Default")
      (node (ref "U12") (pin "11") (pinfunction "Y4_11") (pintype "output"))
      (node (ref "U9") (pin "1") (pinfunction "G_1") (pintype "input"))
      (node (ref "U9") (pin "19") (pinfunction "G_19") (pintype "input"))
    )
    (net (code "189") (name "~{INT_RTC}") (class "Default")
      (node (ref "JP3") (pin "1") (pinfunction "1_1") (pintype "passive"))
      (node (ref "U4") (pin "5") (pinfunction "~{INT}_5") (pintype "open_collector"))
    )
    (net (code "190") (name "~{IRQX}") (class "Default")
      (node (ref "CE0") (pin "52") (pinfunction "~{IRQX}_52") (pintype "bidirectional"))
      (node (ref "U8") (pin "8") (pinfunction "O_8") (pintype "output"))
    )
    (net (code "191") (name "~{RD}") (class "Default")
      (node (ref "CF1") (pin "34") (pinfunction "~{IORD}_34") (pintype "input"))
      (node (ref "U1") (pin "22") (pinfunction "~{OE}_22") (pintype "input"))
      (node (ref "U12") (pin "5") (pinfunction "G2B_5") (pintype "input"))
      (node (ref "U13") (pin "16") (pinfunction "Y2_16") (pintype "tri_state"))
      (node (ref "U16") (pin "1") (pinfunction "DIR_1") (pintype "input"))
      (node (ref "U2") (pin "24") (pinfunction "~{OE}_24") (pintype "input"))
      (node (ref "U3") (pin "24") (pinfunction "~{OE}_24") (pintype "input"))
      (node (ref "U4") (pin "22") (pinfunction "~{OE}_22") (pintype "input"))
    )
    (net (code "192") (name "~{RST}") (class "Default")
      (node (ref "CE0") (pin "14") (pinfunction "~{RST}_14") (pintype "bidirectional"))
      (node (ref "CF1") (pin "41") (pinfunction "/RESET_41") (pintype "input"))
      (node (ref "JP2") (pin "2") (pinfunction "2_2") (pintype "passive"))
    )
    (net (code "193") (name "~{SR_CF}") (class "Default")
      (node (ref "U7") (pin "11") (pinfunction "I2_11") (pintype "input"))
      (node (ref "U8") (pin "4") (pinfunction "O_4") (pintype "output"))
      (node (ref "U9") (pin "2") (pinfunction "A1_2") (pintype "input"))
    )
    (net (code "194") (name "~{SR_RTC}") (class "Default")
      (node (ref "JP3") (pin "2") (pinfunction "2_2") (pintype "passive"))
      (node (ref "R4") (pin "1") (pinfunction "1_1") (pintype "passive"))
      (node (ref "U7") (pin "10") (pinfunction "I1_10") (pintype "input"))
      (node (ref "U9") (pin "17") (pinfunction "A4_17") (pintype "input"))
    )
    (net (code "195") (name "~{U3CS}") (class "Default")
      (node (ref "R3") (pin "2") (pinfunction "2_2") (pintype "passive"))
      (node (ref "U1") (pin "20") (pinfunction "~{CE}_20") (pintype "input"))
      (node (ref "U5") (pin "19") (pinfunction "P=Q_19") (pintype "output"))
      (node (ref "U7") (pin "2") (pinfunction "I1_2") (pintype "input"))
      (node (ref "U7") (pin "4") (pinfunction "I1_4") (pintype "input"))
    )
    (net (code "196") (name "~{WAIT}") (class "Default")
      (node (ref "CE0") (pin "18") (pinfunction "~{WAIT}_18") (pintype "bidirectional"))
      (node (ref "JP4") (pin "1") (pinfunction "1_1") (pintype "passive"))
    )
    (net (code "197") (name "~{WR}") (class "Default")
      (node (ref "CF1") (pin "35") (pinfunction "~{IOWR}_35") (pintype "input"))
      (node (ref "U13") (pin "14") (pinfunction "Y3_14") (pintype "tri_state"))
      (node (ref "U2") (pin "29") (pinfunction "~{WE}_29") (pintype "input"))
      (node (ref "U3") (pin "29") (pinfunction "~{WE}_29") (pintype "input"))
      (node (ref "U4") (pin "27") (pinfunction "~{WE}_27") (pintype "input"))
    )
  )
)
